# Bidirectional_Amp.net
KiCad netlist of a schematic drawn in EAGLE
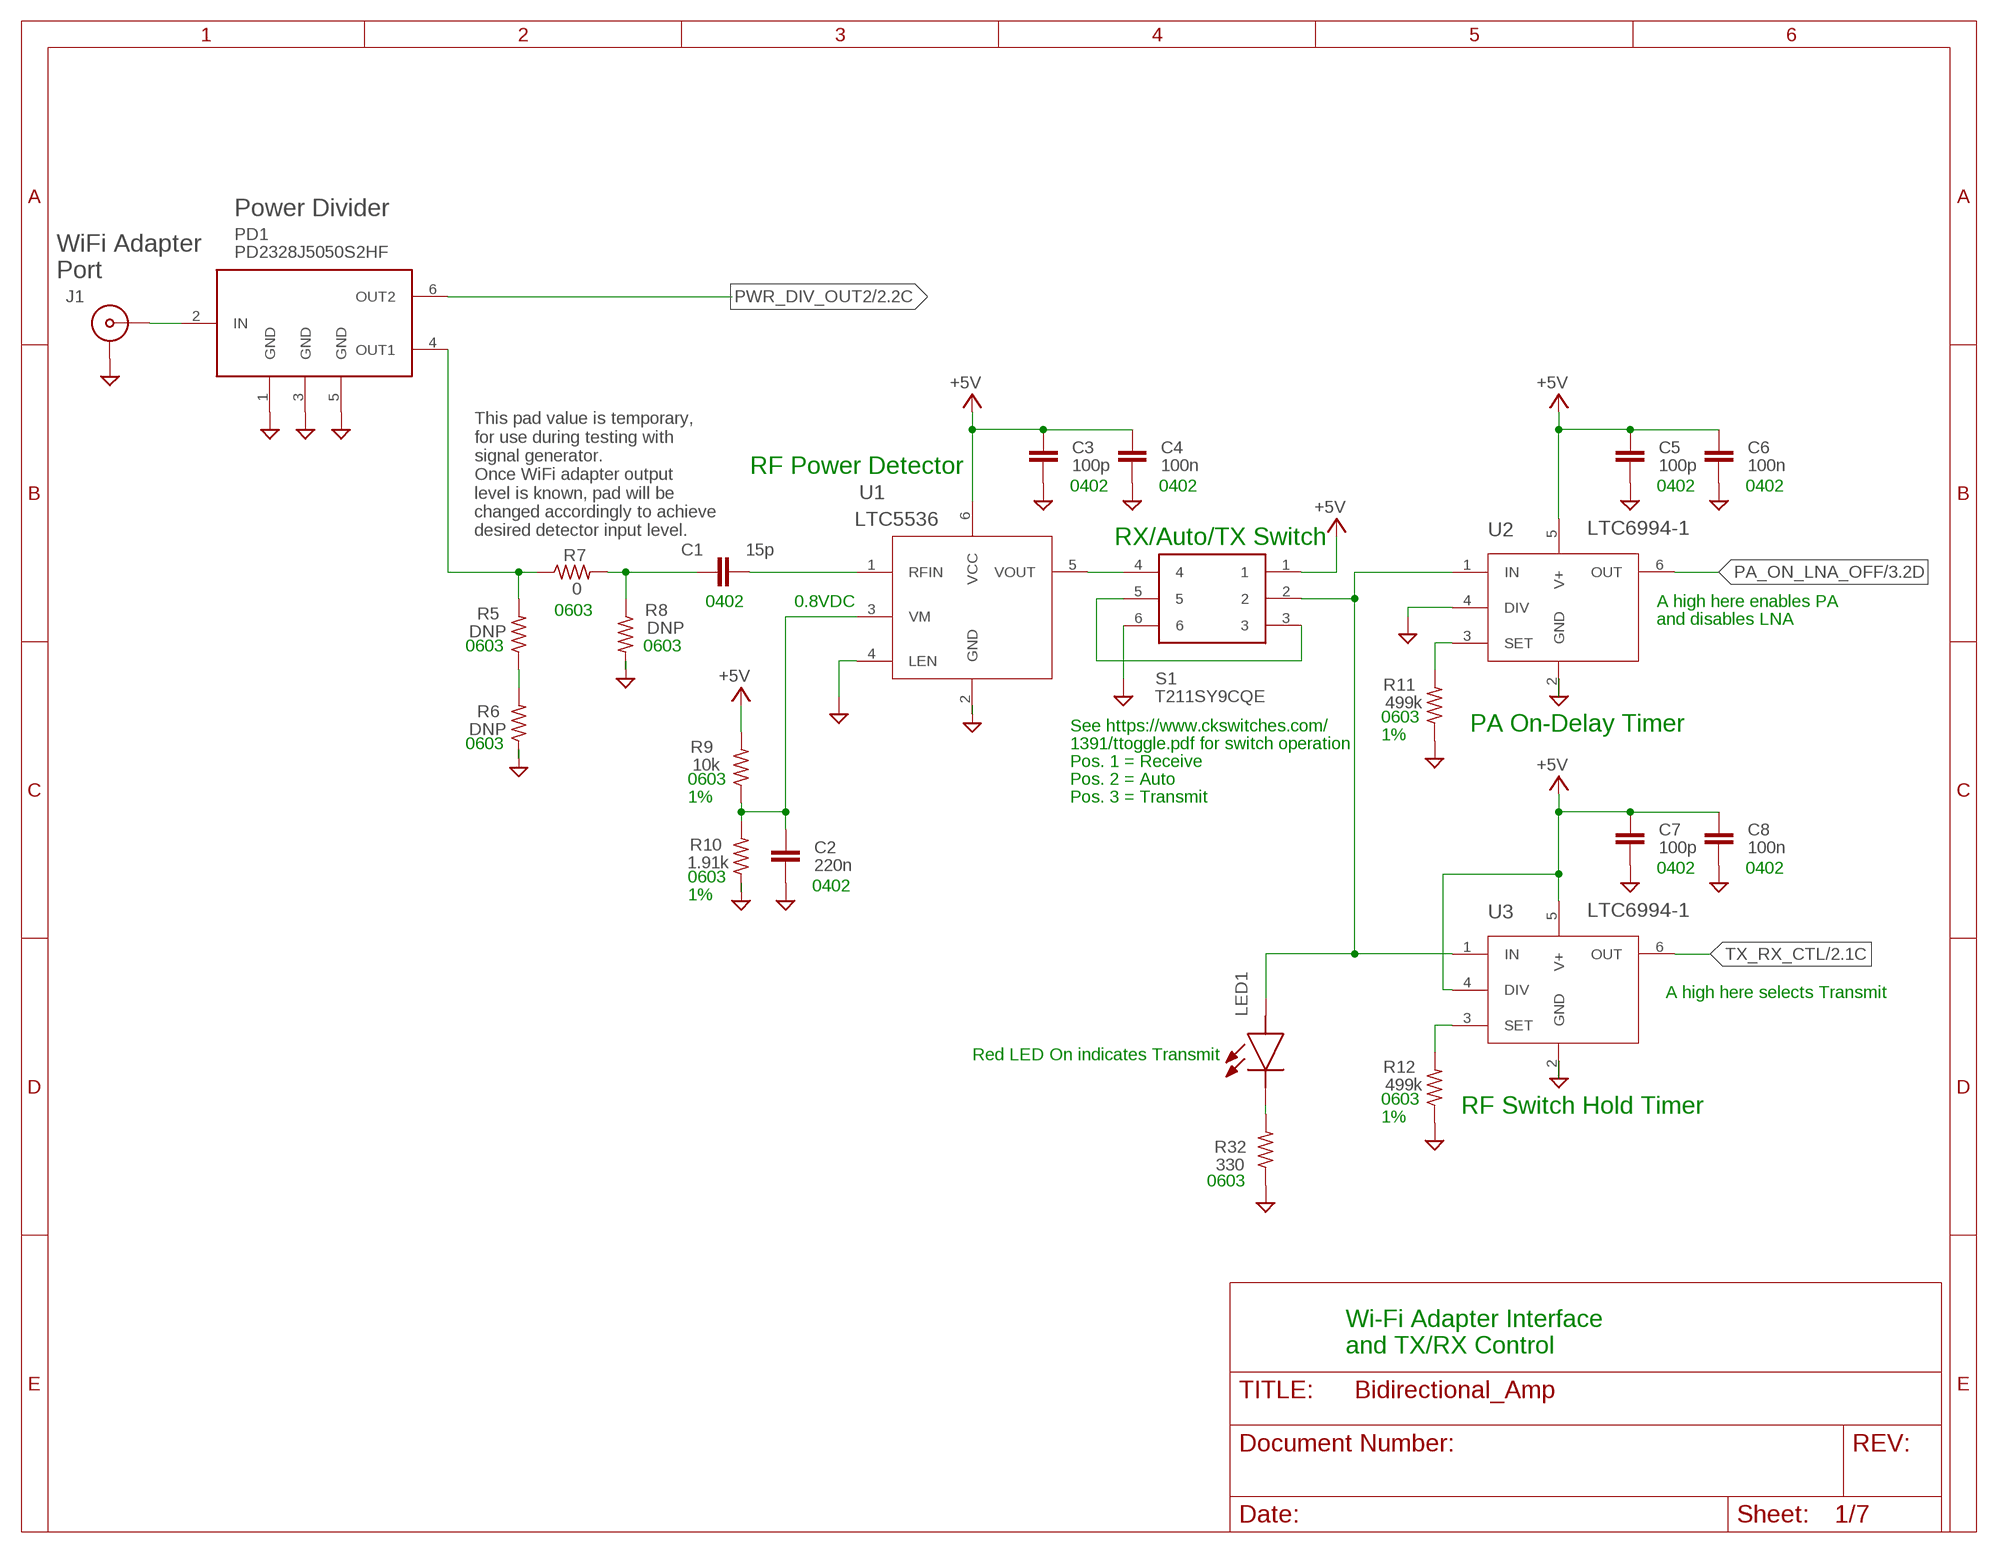
[diagram p0: schematic, sheet 1]
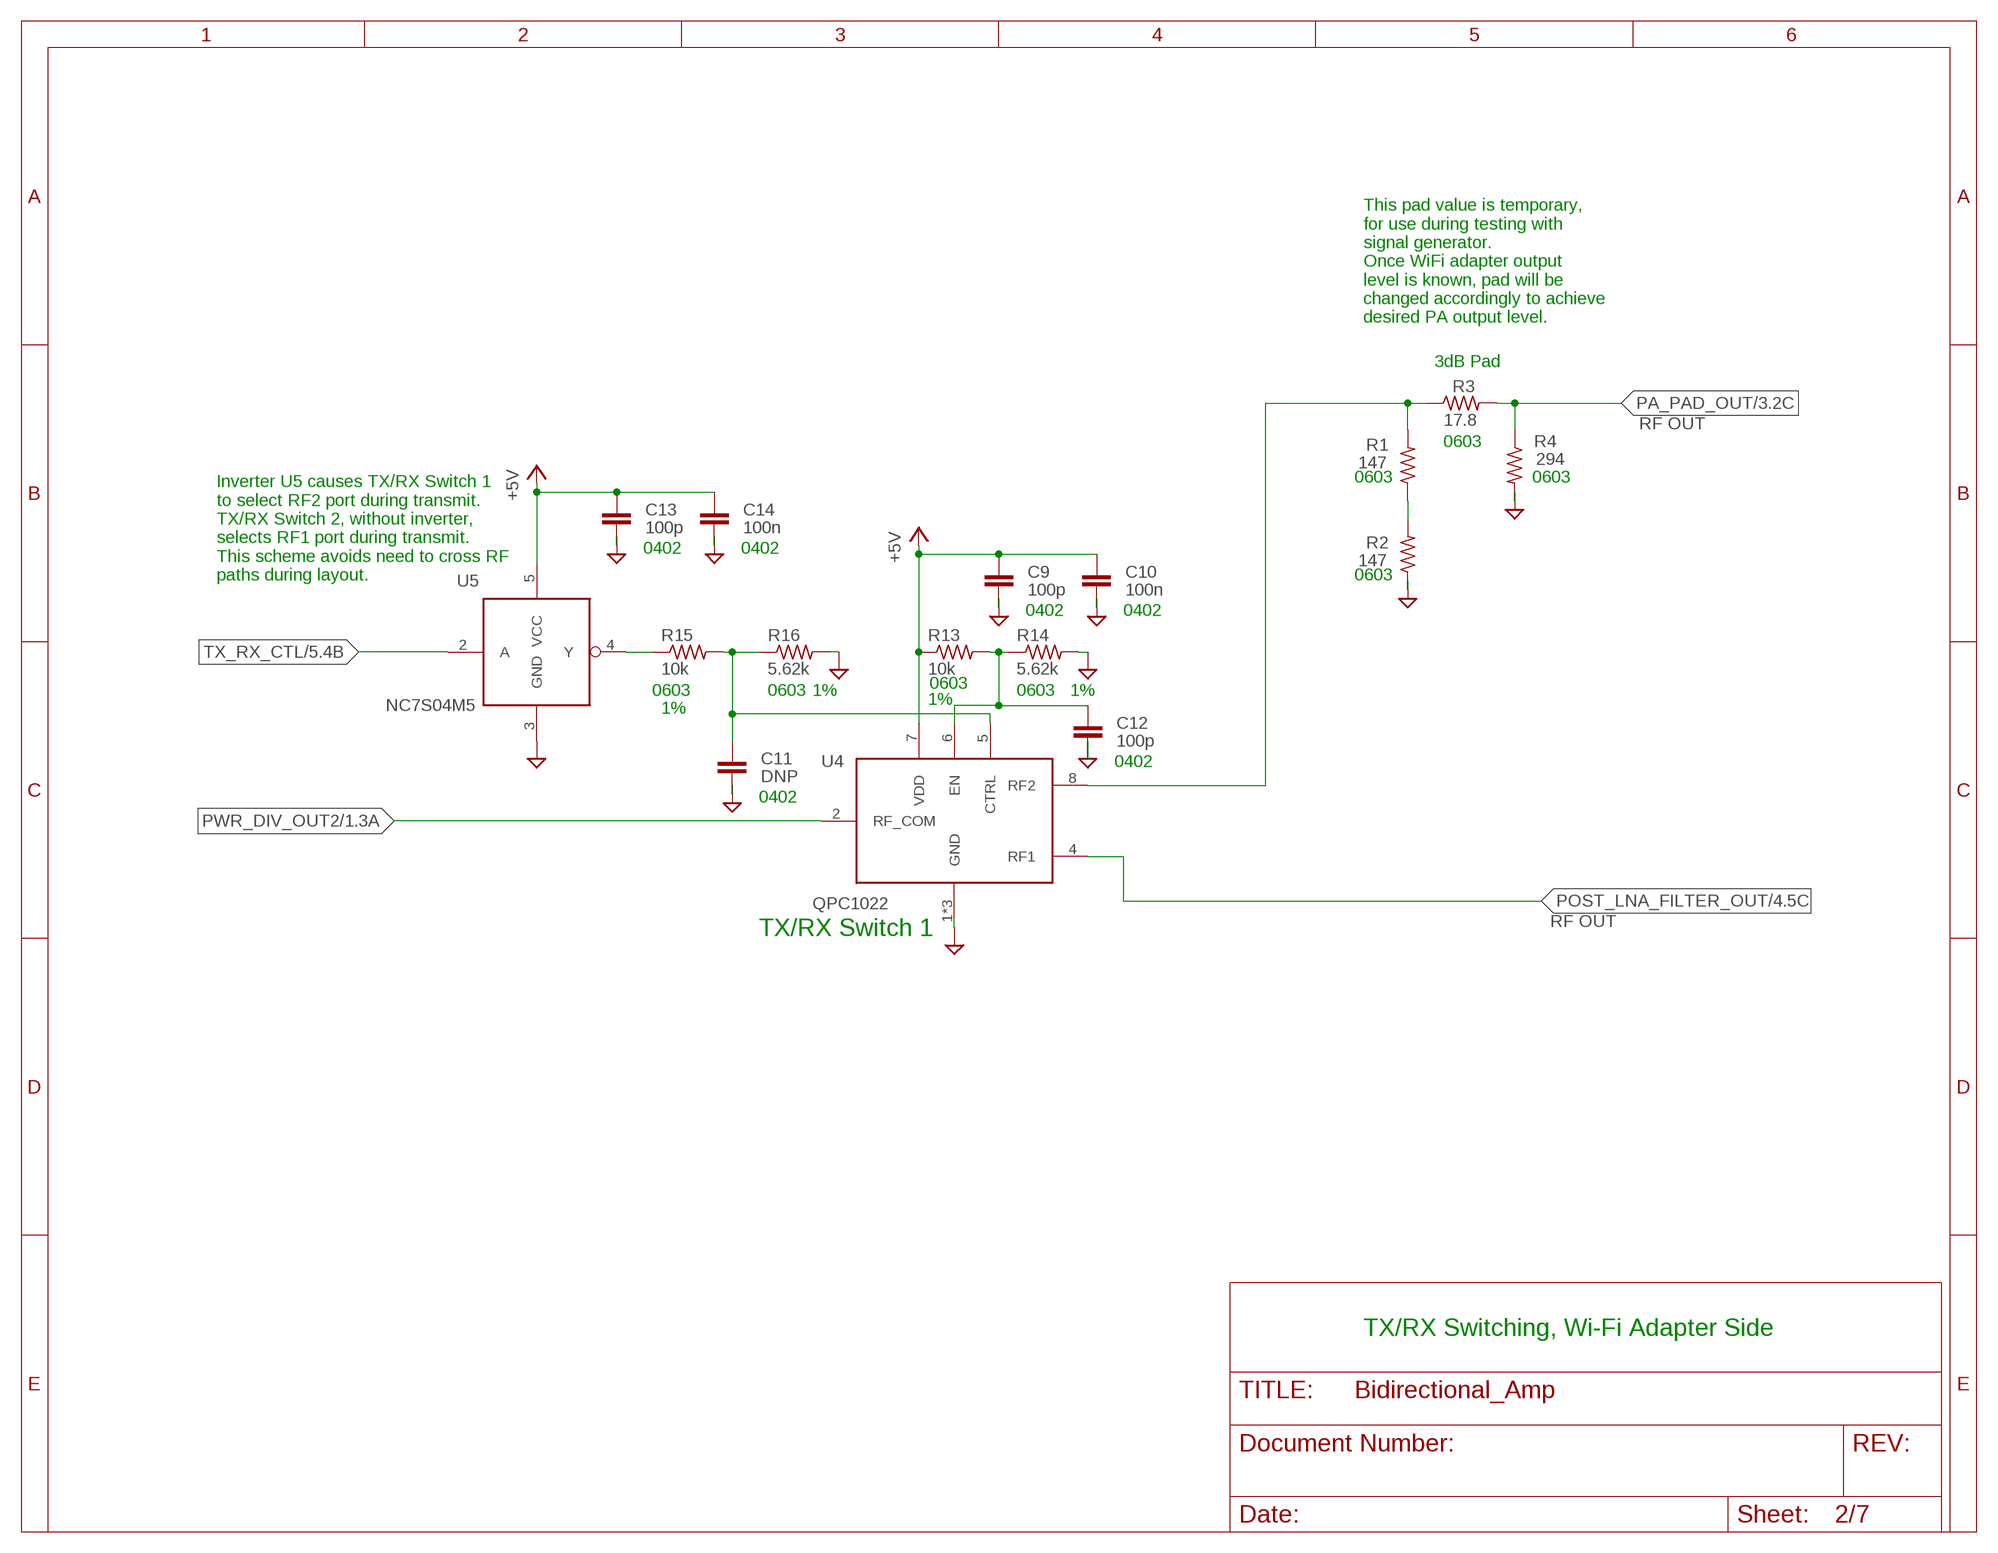
[diagram p1: schematic, sheet 2]
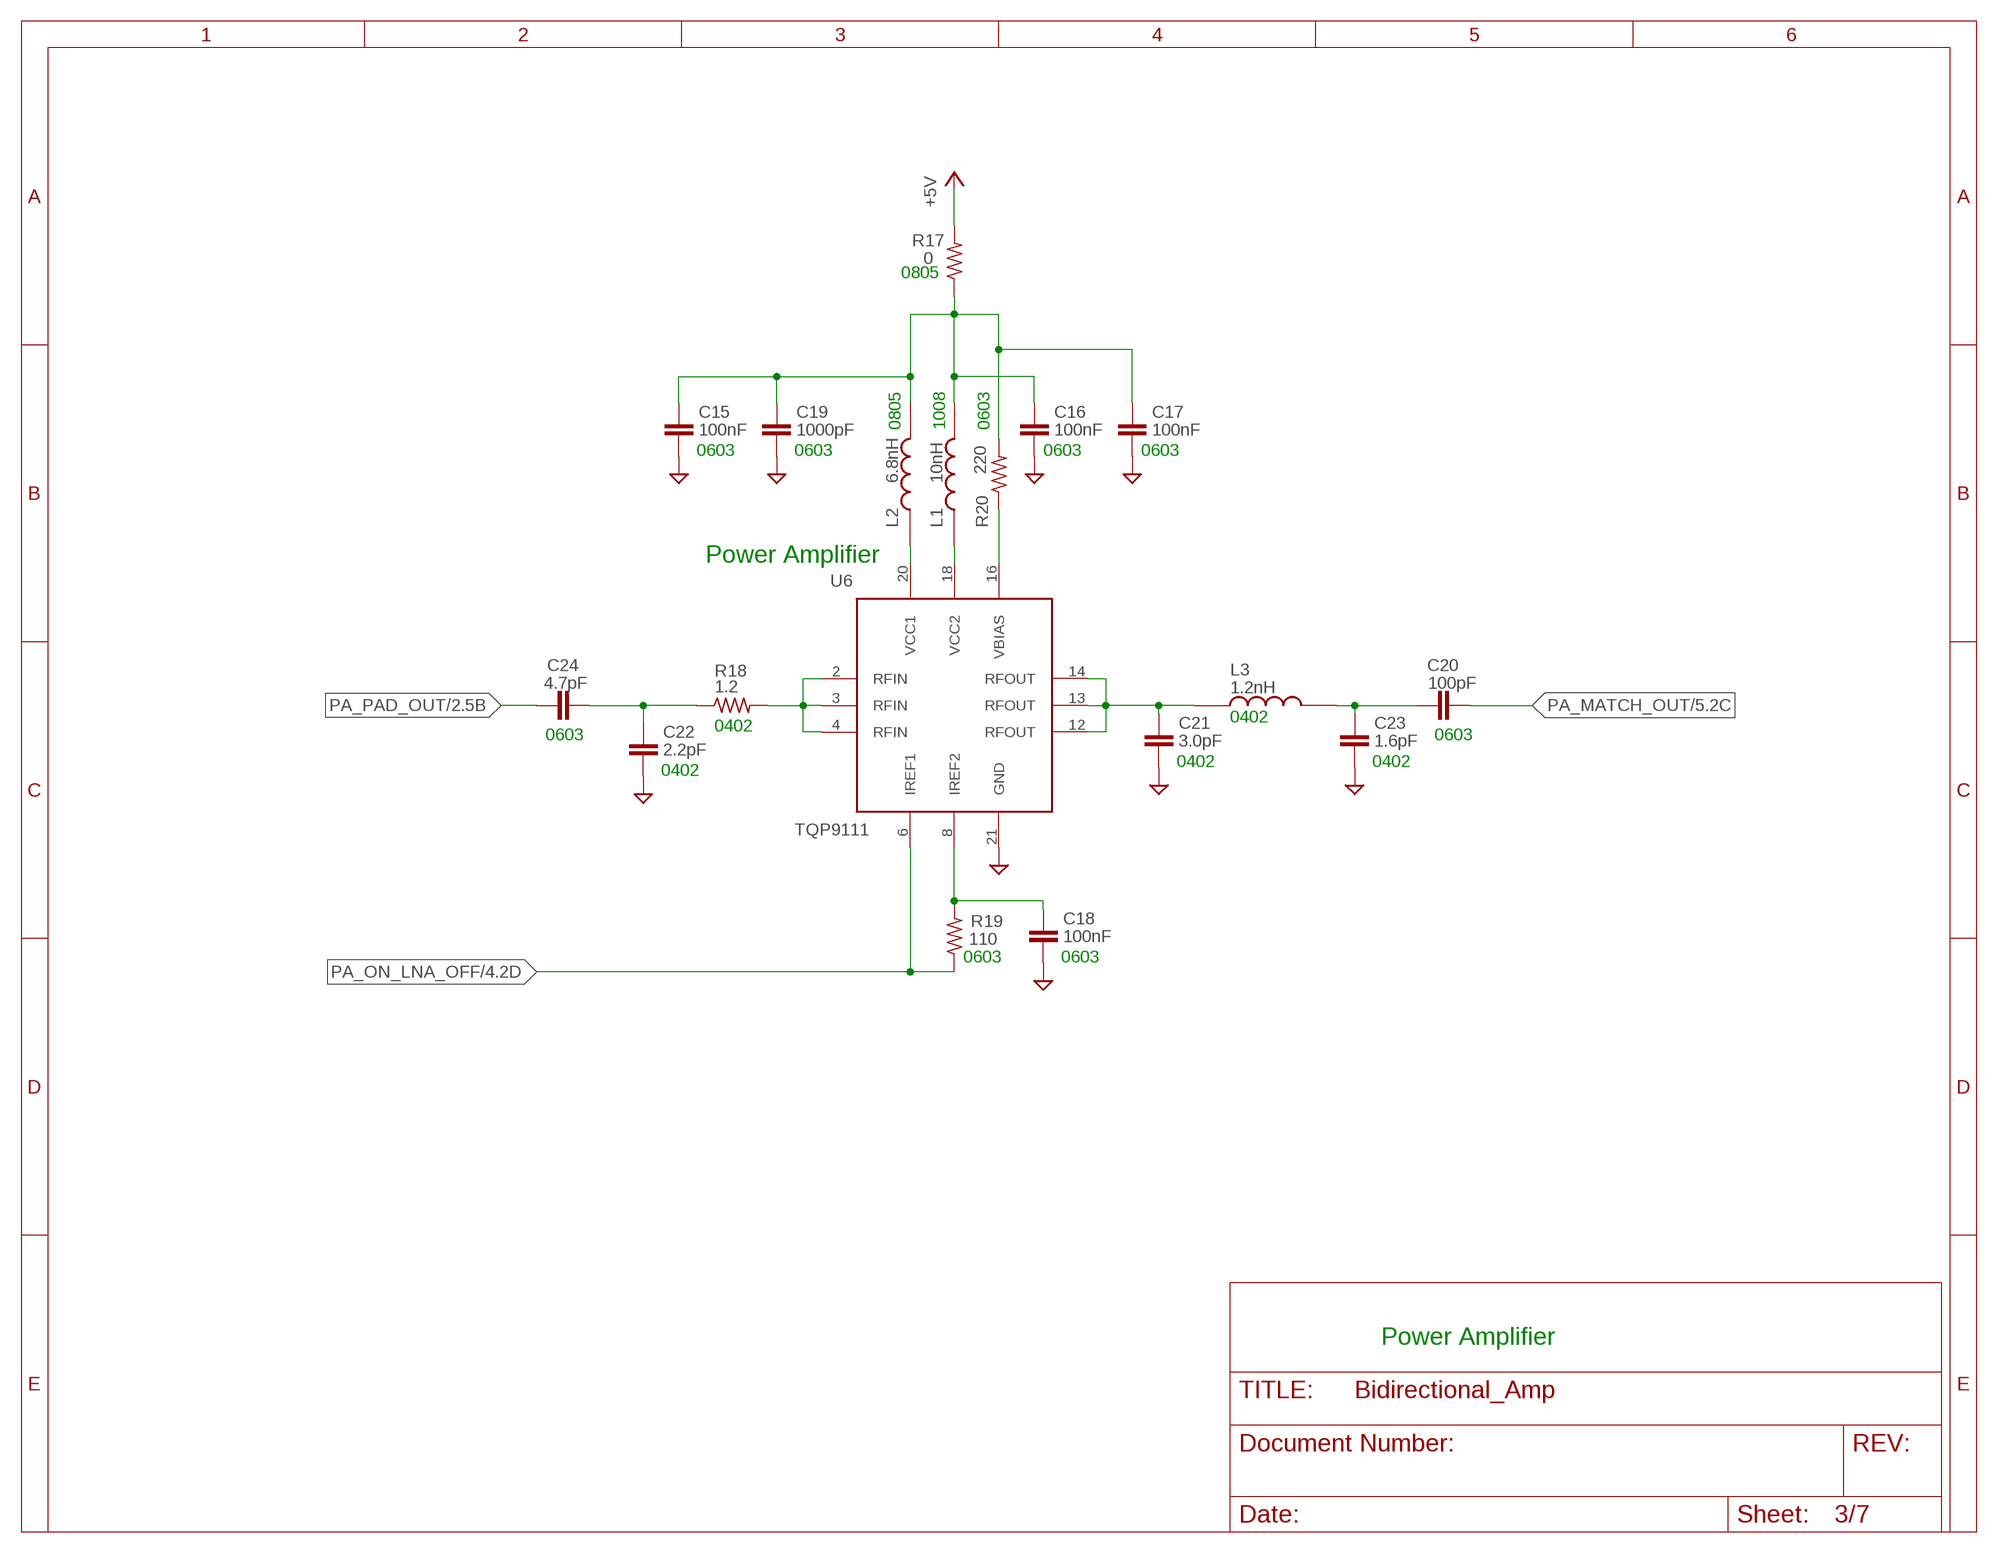
[diagram p2: schematic, sheet 3]
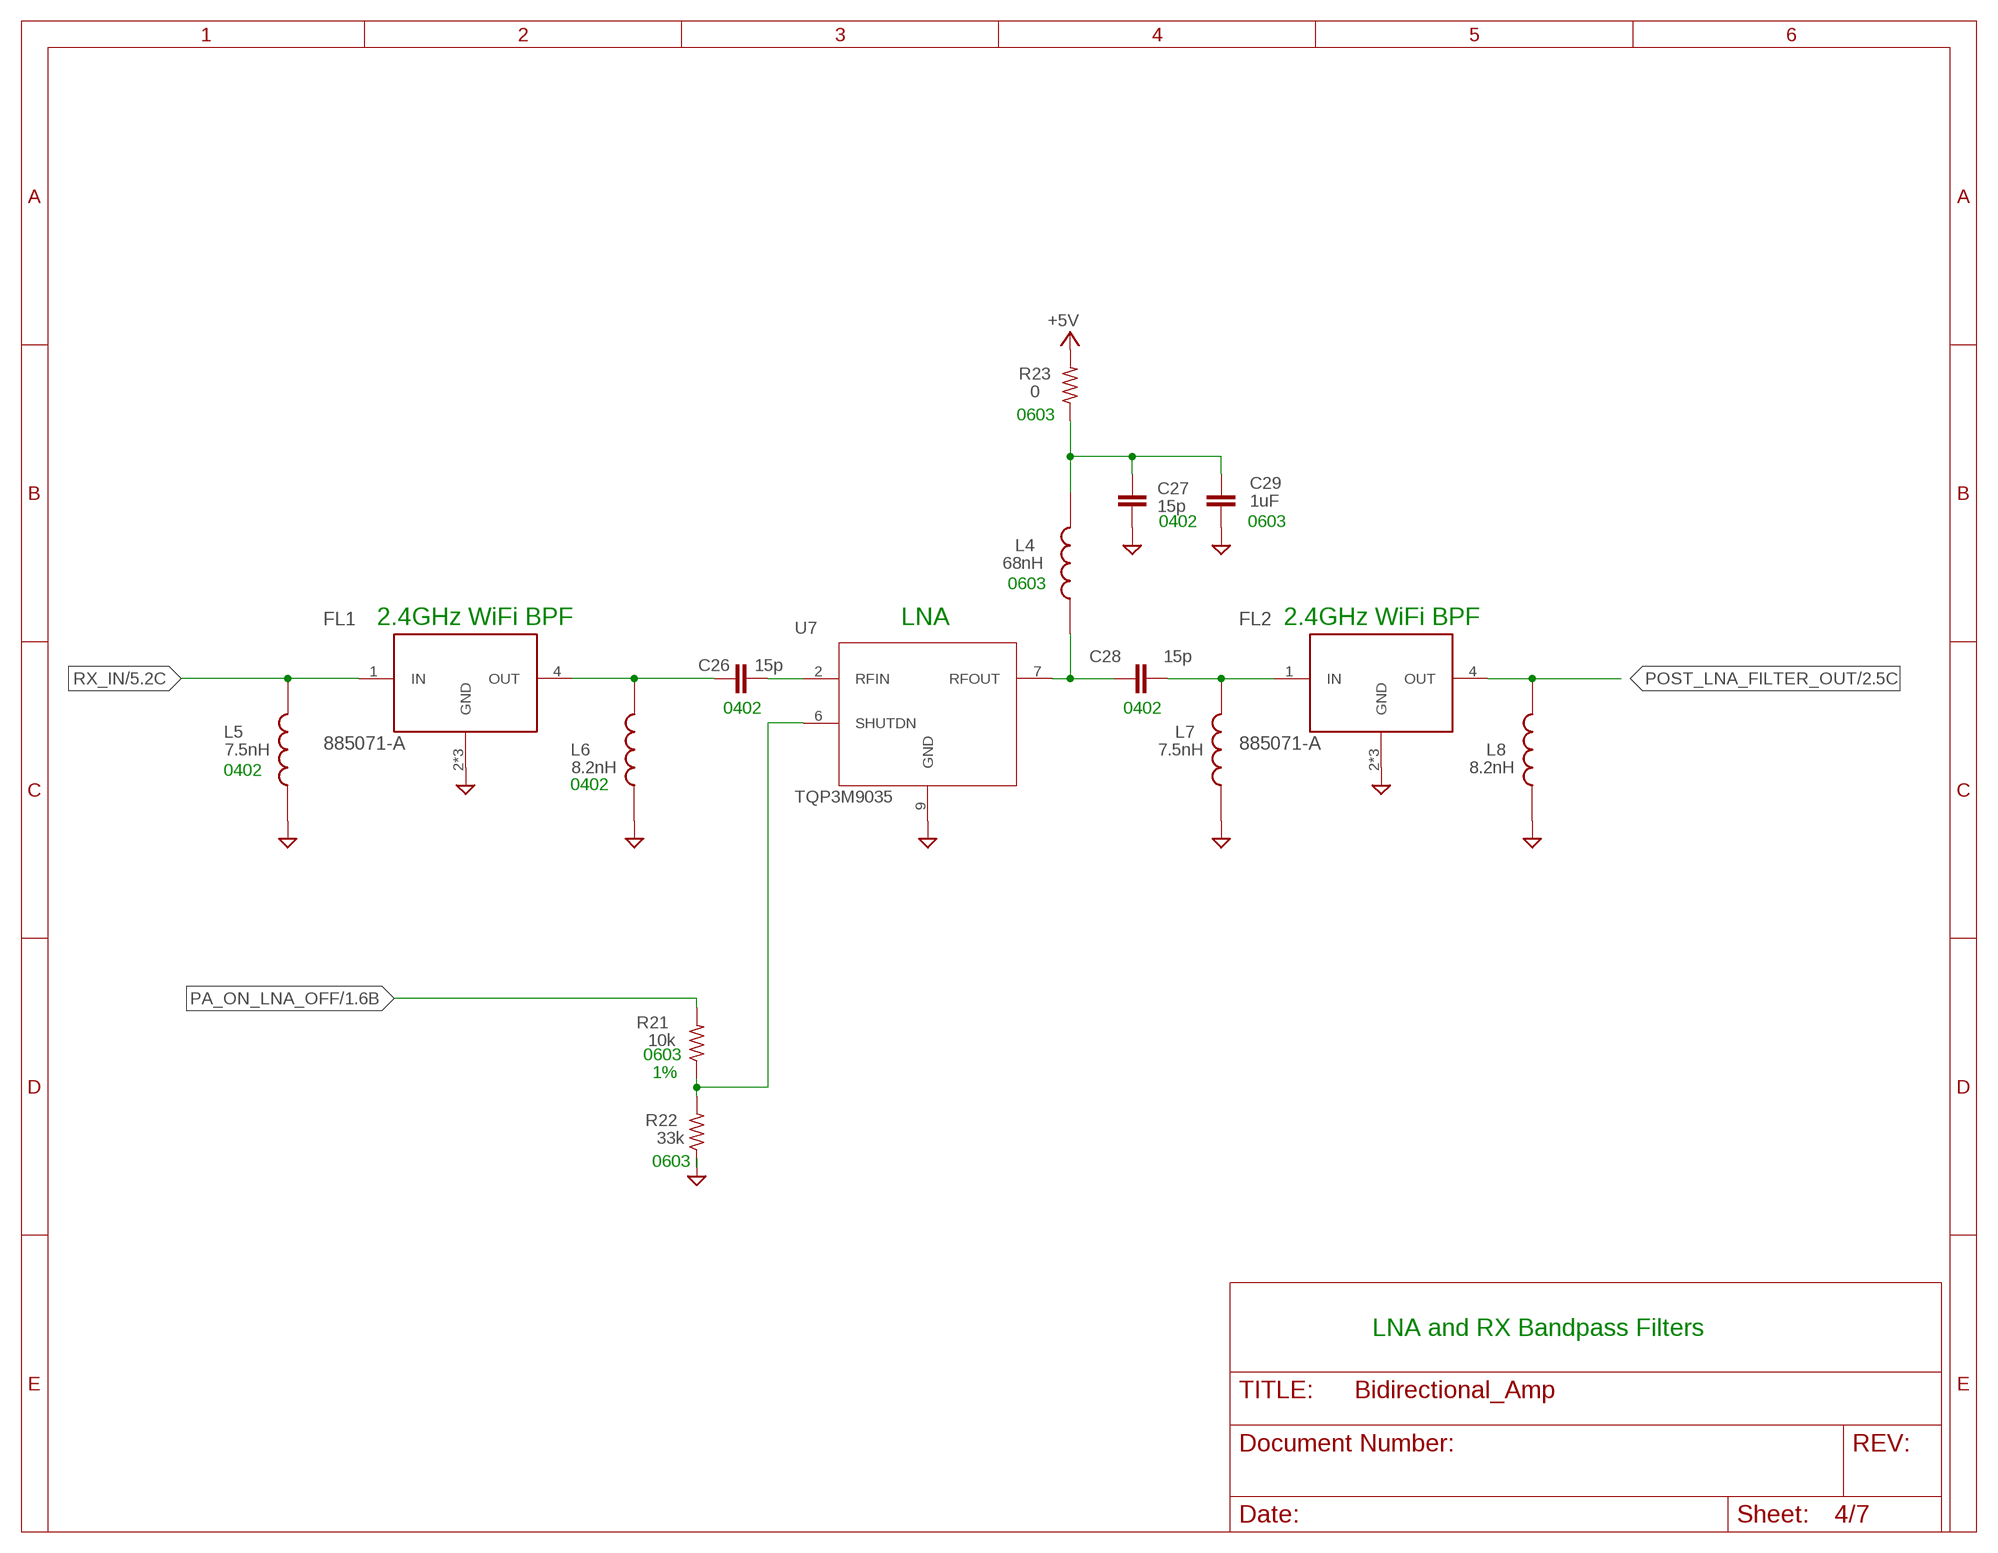
[diagram p3: schematic, sheet 4]
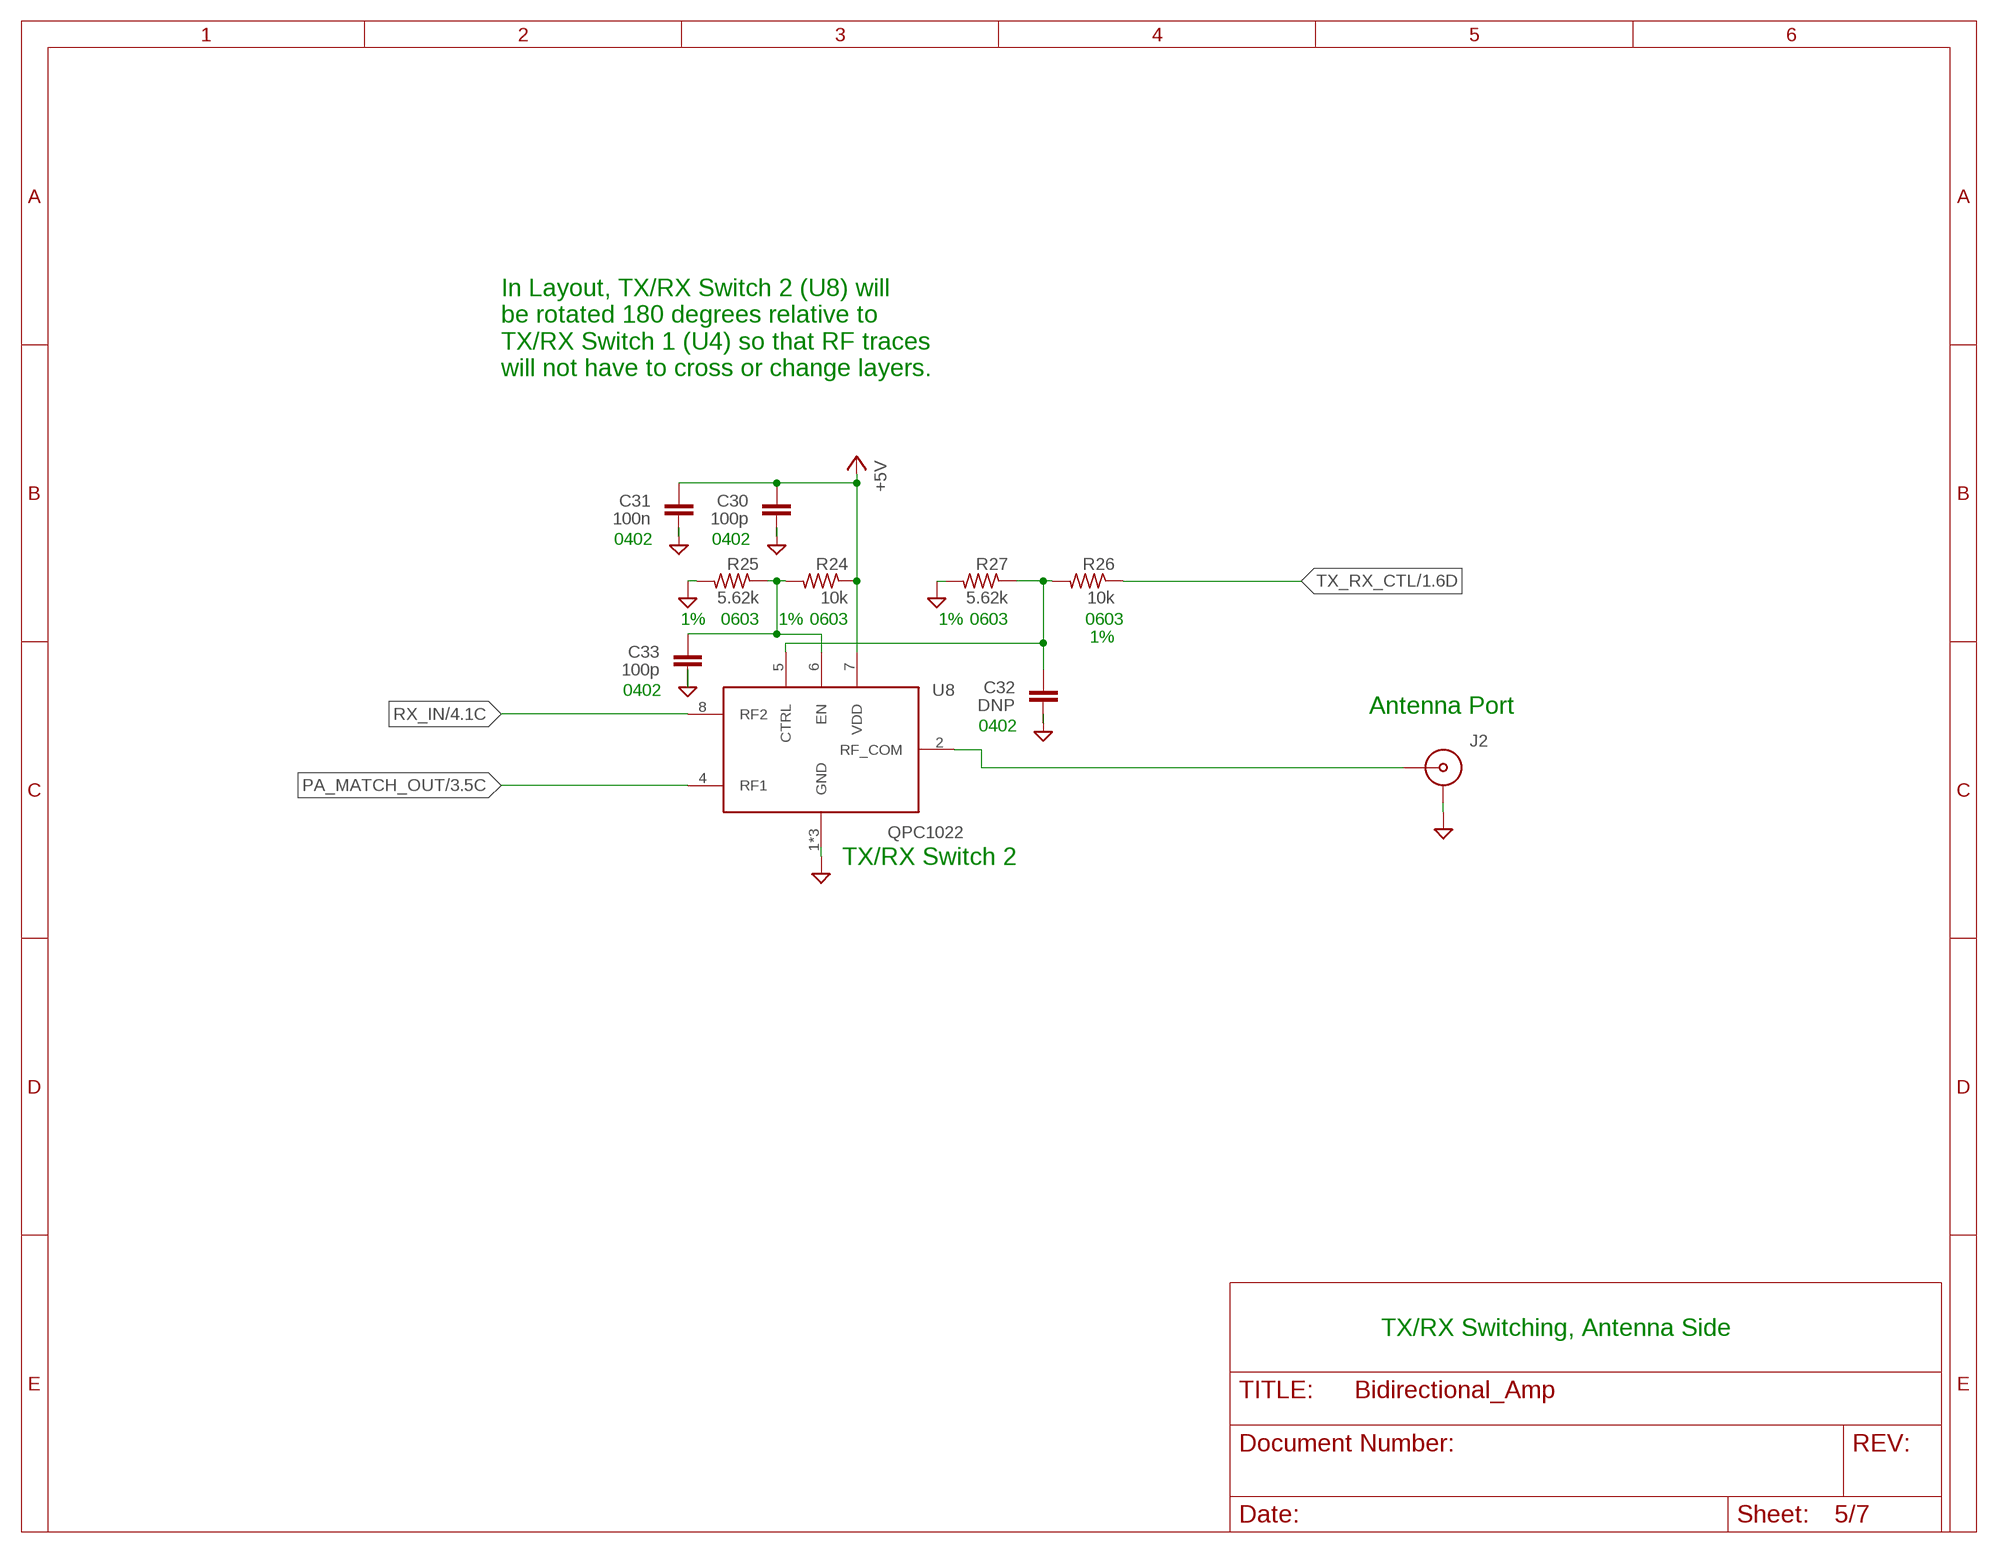
[diagram p4: schematic, sheet 5]
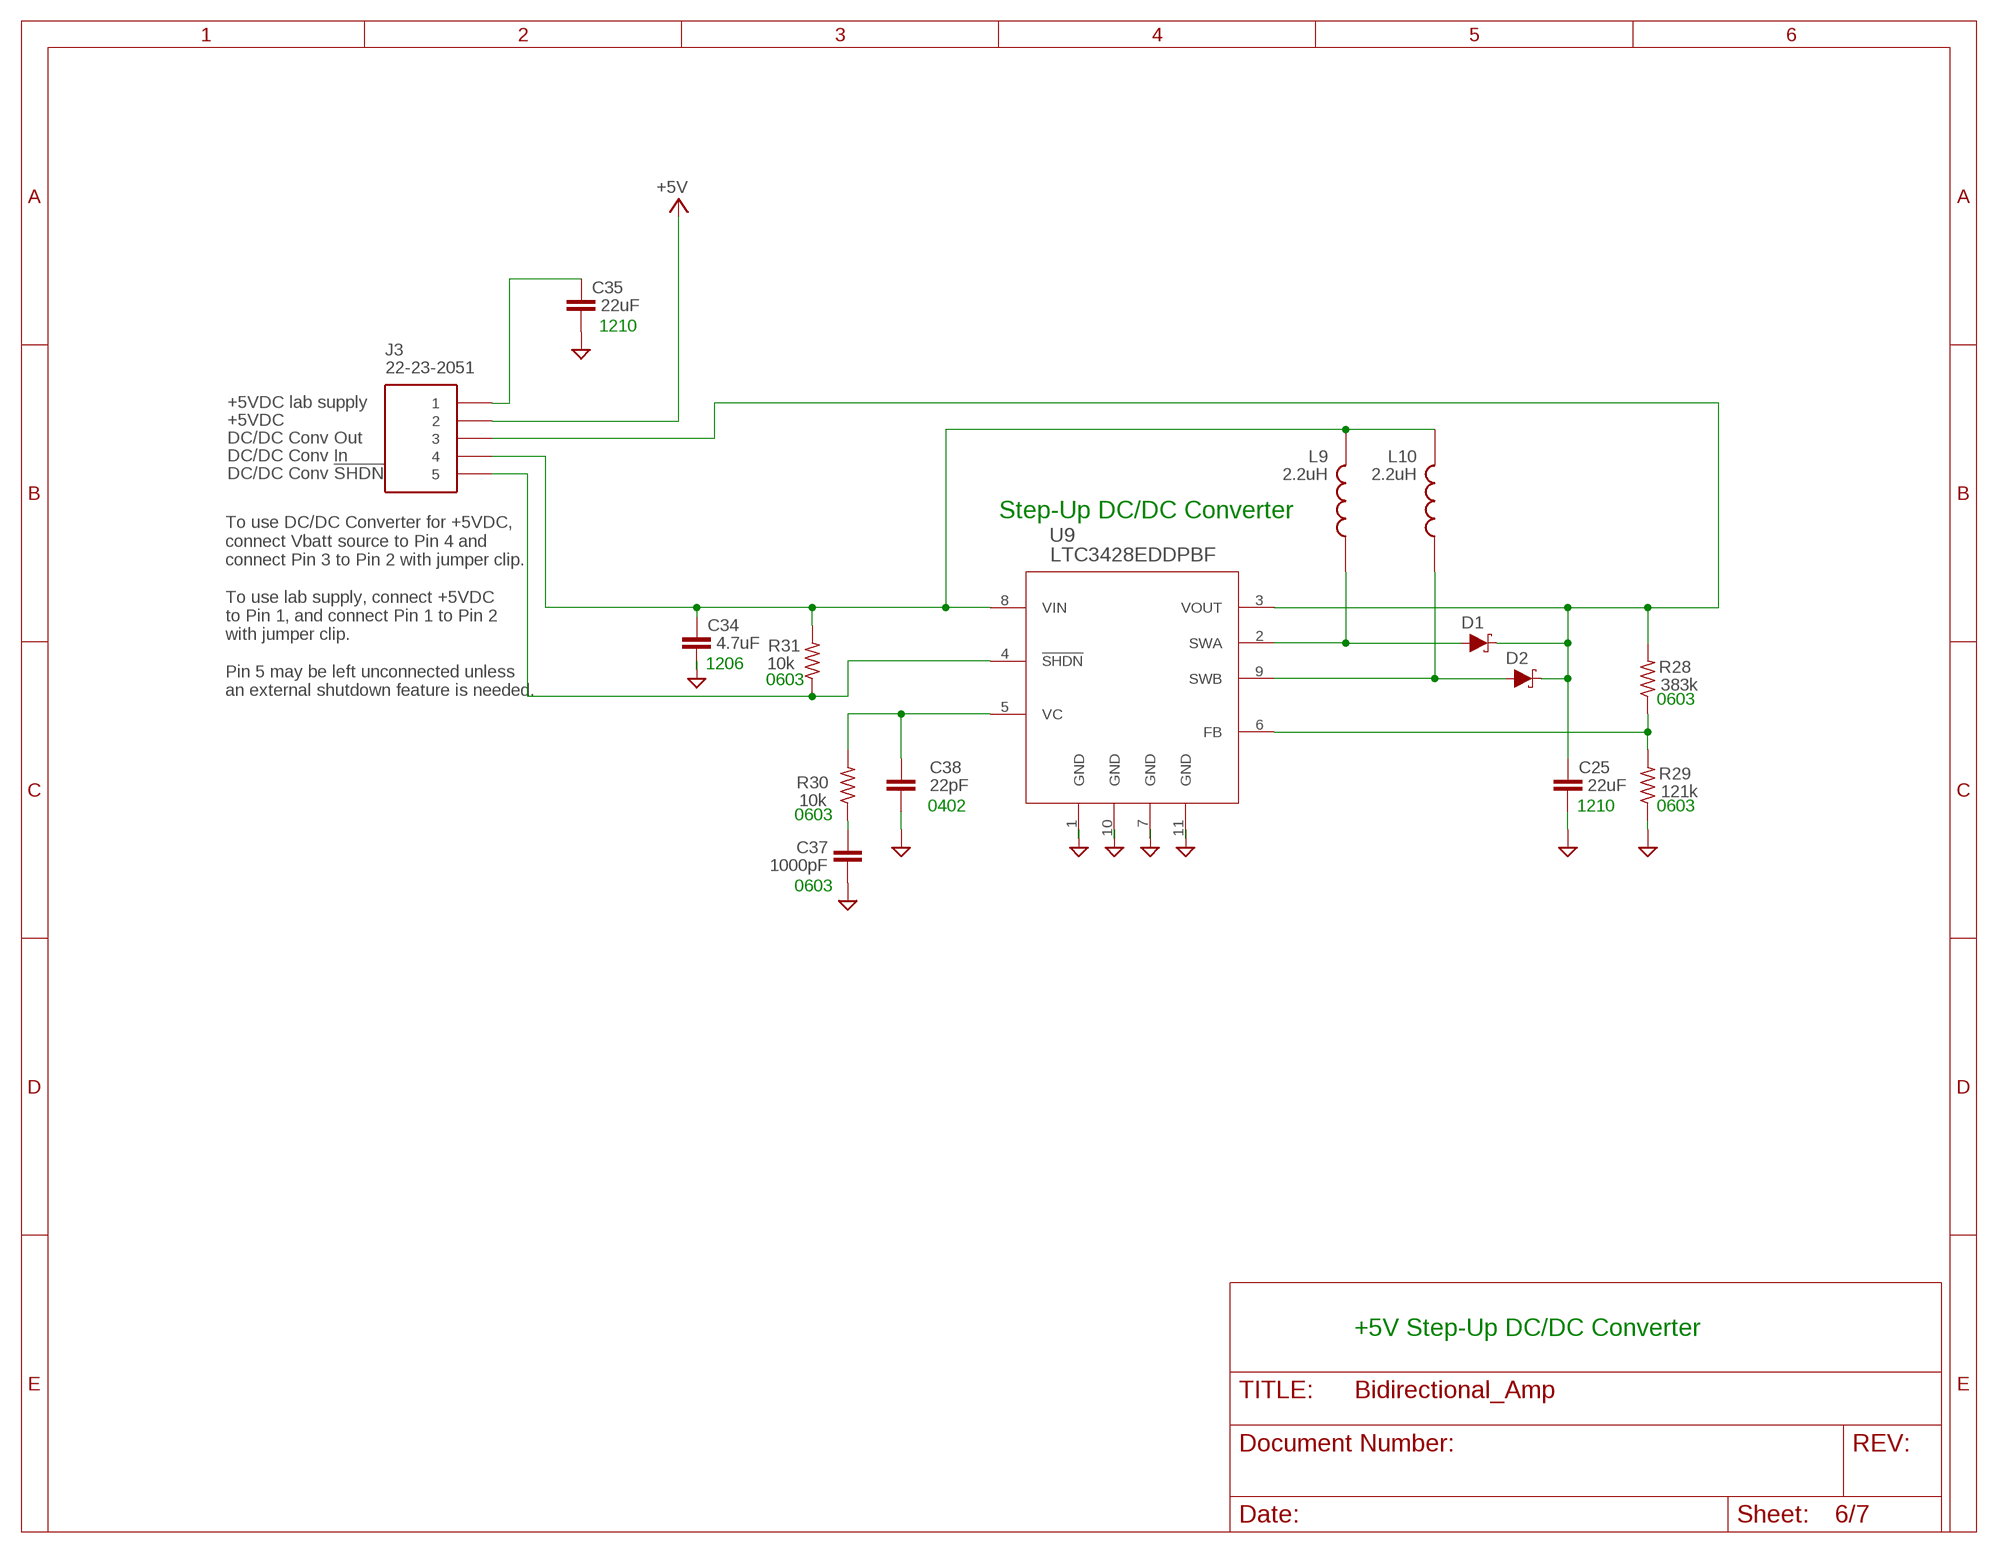
[diagram p5: schematic, sheet 6]
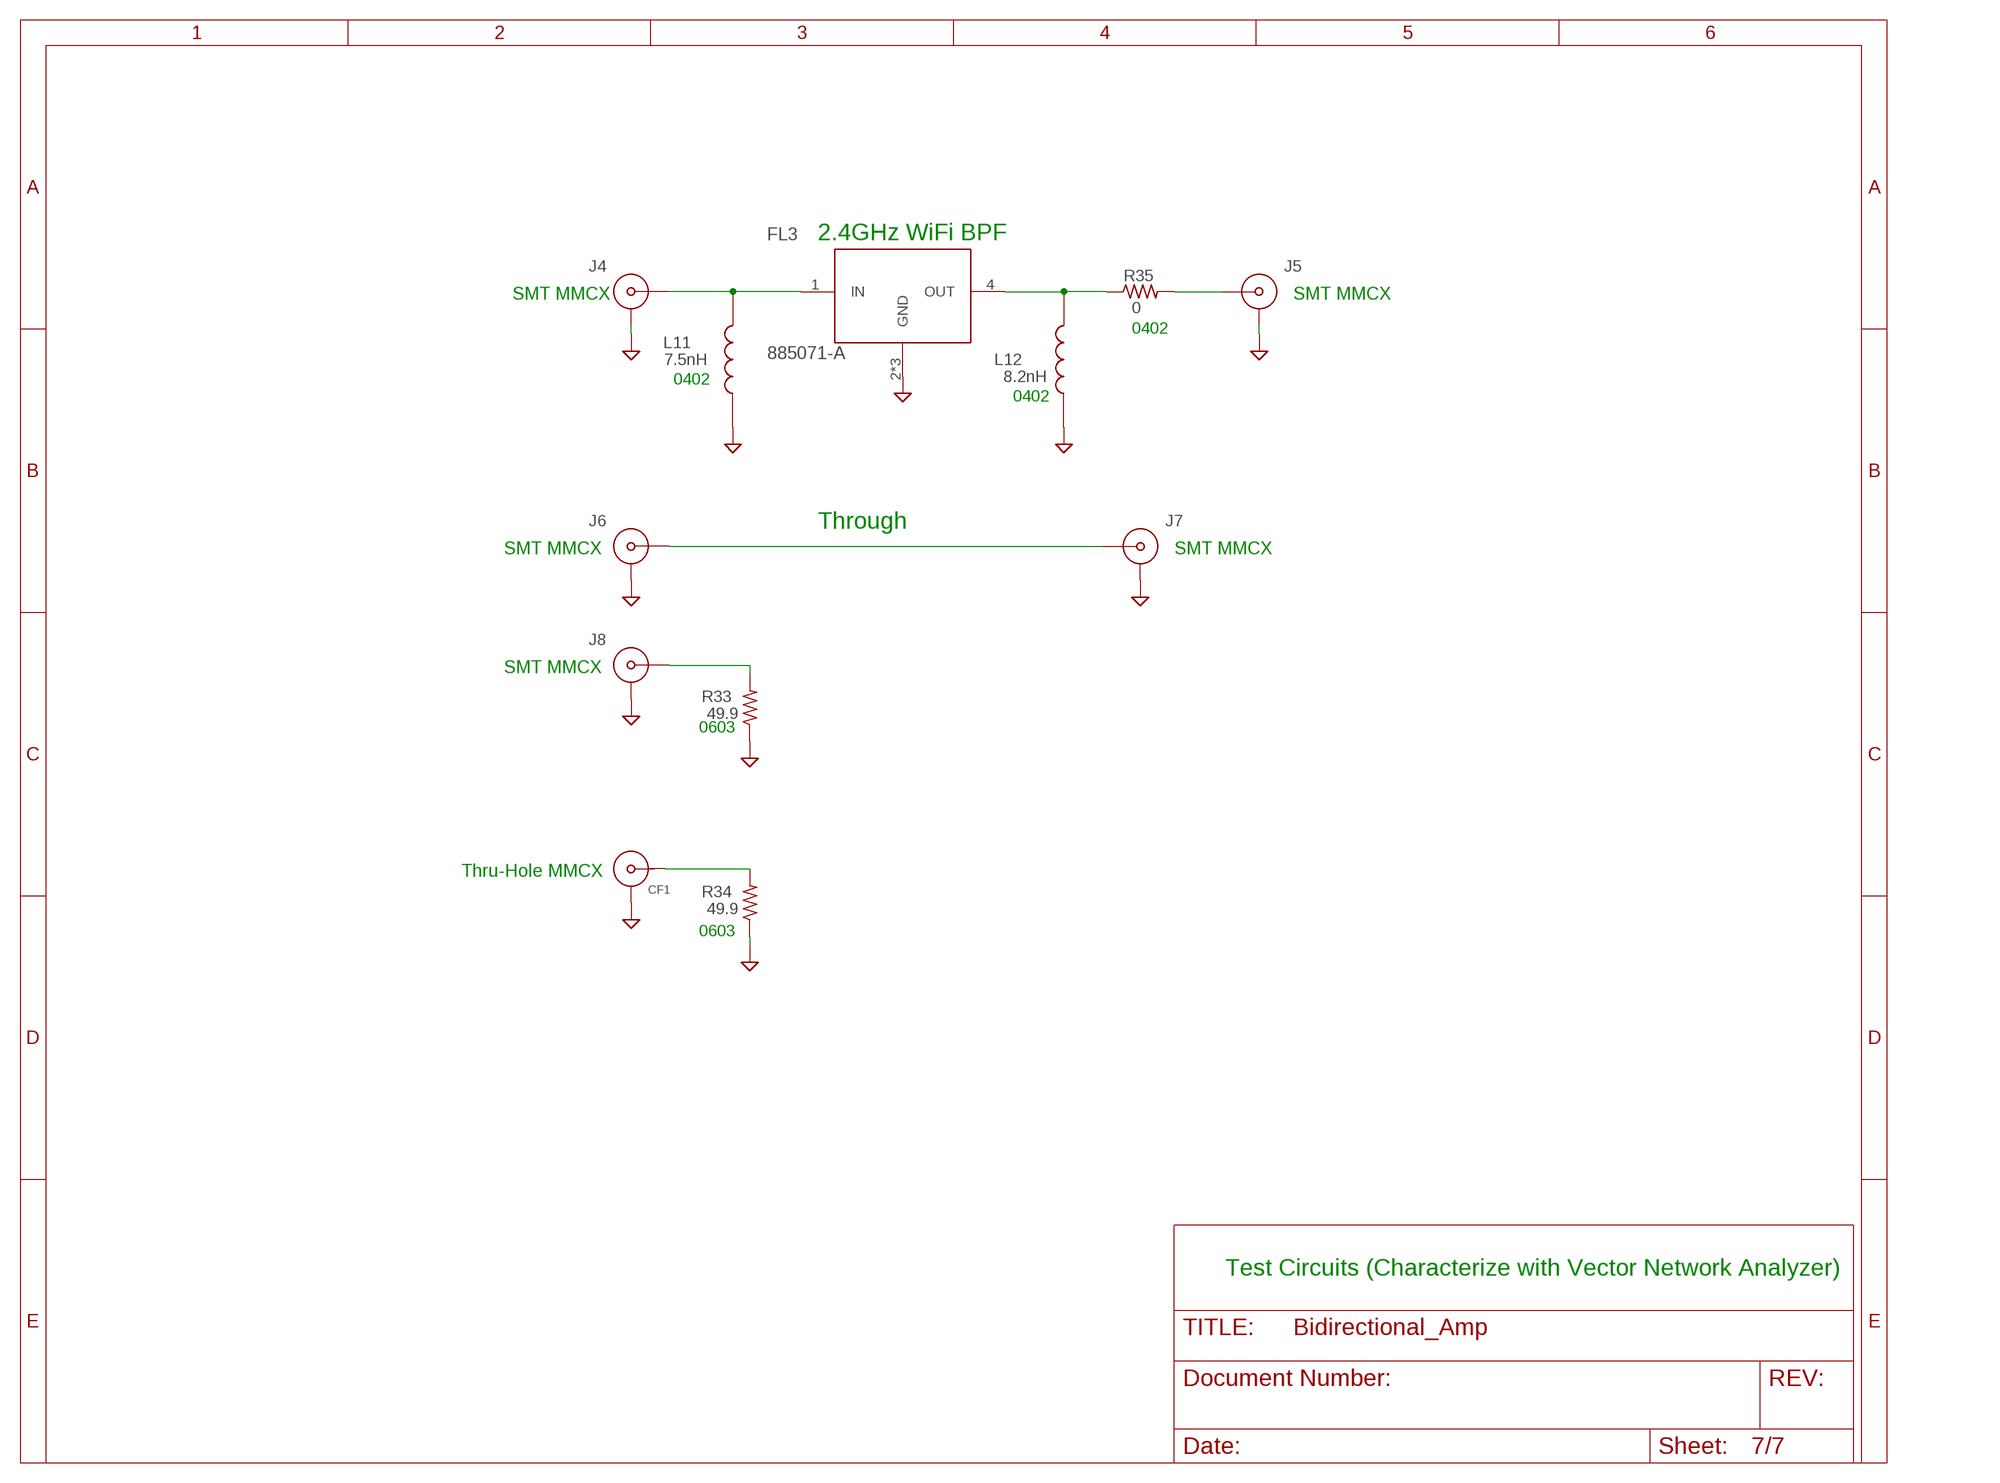
[diagram p6: schematic, sheet 7]

(export (version "E")
  (design (tool "Eeschema 10.0.6"))
  (components
    (comp (ref "C25")
      (value "22uF")
      (footprint "eagle-import:C1210")
      (fields (field (name "MPN") "GCJ32ER71C226KE01L"))
      (libsource (lib "eagle-import") (part "C-EUC1210"))
    )
    (comp (ref "C34")
      (value "4.7uF")
      (footprint "eagle-import:C1206")
      (fields (field (name "MPN") "GCJ31CR71C475KA01L") (field (name "VOLTAGE") "16V"))
      (libsource (lib "eagle-import") (part "C-EUC1206"))
    )
    (comp (ref "C35")
      (value "22uF")
      (footprint "eagle-import:C1210")
      (fields (field (name "MPN") "GCJ32ER71C226KE01L"))
      (libsource (lib "eagle-import") (part "C-EUC1210"))
    )
    (comp (ref "C37")
      (value "1000pF")
      (footprint "eagle-import:C0603")
      (fields (field (name "MPN") "CGA3E2C0G1H102J080AA"))
      (libsource (lib "eagle-import") (part "C-EUC0603"))
    )
    (comp (ref "C38")
      (value "22pF")
      (footprint "eagle-import:C0402")
      (fields (field (name "MPN") "GCM1555C1H220JA16J"))
      (libsource (lib "eagle-import") (part "C-EUC0402"))
    )
    (comp (ref "D1")
      (value "DIODE-SCHOTTKY-PMEG4005EJ")
      (footprint "eagle-import:SOD-323")
      (fields (field (name "MPN") "PMEG1020EJ,115"))
      (libsource (lib "eagle-import") (part "DIODE-SCHOTTKY-PMEG4005EJ"))
    )
    (comp (ref "D2")
      (value "DIODE-SCHOTTKY-PMEG4005EJ")
      (footprint "eagle-import:SOD-323")
      (fields (field (name "MPN") "PMEG1020EJ,115"))
      (libsource (lib "eagle-import") (part "DIODE-SCHOTTKY-PMEG4005EJ"))
    )
    (comp (ref "J3")
      (value "22-23-2051")
      (footprint "eagle-import:HDRV5W107P0X254_1X5_1255X635X8")
      (libsource (lib "eagle-import") (part "22-23-2051"))
    )
    (comp (ref "L9")
      (value "2.2uH")
      (footprint "eagle-import:XFL4020-222ME")
      (fields (field (name "MANUFACTURER_PART_NUMBER") "XFL4020-222MEB"))
      (libsource (lib "eagle-import") (part "XFL4020-222MEB"))
    )
    (comp (ref "L10")
      (value "2.2uH")
      (footprint "eagle-import:XFL4020-222ME")
      (fields (field (name "MANUFACTURER_PART_NUMBER") "XFL4020-222MEB"))
      (libsource (lib "eagle-import") (part "XFL4020-222MEB"))
    )
    (comp (ref "R28")
      (value "383k")
      (footprint "eagle-import:.0603-B-NOSILK")
      (fields (field (name "MPN") "ERJ-3EKF3833V"))
      (libsource (lib "eagle-import") (part "rcl_custom_R-US_0603-B-NOSILK"))
    )
    (comp (ref "R29")
      (value "121k")
      (footprint "eagle-import:.0603-B-NOSILK")
      (fields (field (name "MPN") "ERJ-3EKF1213V "))
      (libsource (lib "eagle-import") (part "rcl_custom_R-US_0603-B-NOSILK"))
    )
    (comp (ref "R30")
      (value "10k")
      (footprint "eagle-import:.0603-B-NOSILK")
      (fields (field (name "MPN") "ERJ-3EKF1002V"))
      (libsource (lib "eagle-import") (part "rcl_custom_R-US_0603-B-NOSILK"))
    )
    (comp (ref "R31")
      (value "10k")
      (footprint "eagle-import:.0603-B-NOSILK")
      (fields (field (name "MPN") "ERJ-3GEYJ103V"))
      (libsource (lib "eagle-import") (part "rcl_custom_R-US_0603-B-NOSILK"))
    )
    (comp (ref "U9")
      (value "LTC3428EDDPBF")
      (footprint "eagle-import:DFN-10_DD")
      (fields (field (name "MANUFACTURER_PART_NUMBER") "LTC3428EDD#PBF"))
      (libsource (lib "eagle-import") (part "LTC3428EDDPBF"))
    )
    (comp (ref "C1")
      (value "15p")
      (footprint "eagle-import:C0402")
      (fields (field (name "MPN") "GJM1555C1H150JB01D "))
      (libsource (lib "eagle-import") (part "C-EUC0402"))
    )
    (comp (ref "C2")
      (value "220n")
      (footprint "eagle-import:C0402")
      (fields (field (name "MPN") "C1005X7R1C224K050BE "))
      (libsource (lib "eagle-import") (part "C-EUC0402"))
    )
    (comp (ref "C3")
      (value "100p")
      (footprint "eagle-import:C0402")
      (fields (field (name "MPN") "GCM1555C1H101JA16D "))
      (libsource (lib "eagle-import") (part "C-EUC0402"))
    )
    (comp (ref "C4")
      (value "100n")
      (footprint "eagle-import:C0402")
      (fields (field (name "MPN") "CGA2B1X7R1C104K050BC"))
      (libsource (lib "eagle-import") (part "C-EUC0402"))
    )
    (comp (ref "C5")
      (value "100p")
      (footprint "eagle-import:C0402")
      (fields (field (name "MPN") "GCM1555C1H101JA16D "))
      (libsource (lib "eagle-import") (part "C-EUC0402"))
    )
    (comp (ref "C6")
      (value "100n")
      (footprint "eagle-import:C0402")
      (fields (field (name "MPN") "CGA2B1X7R1C104K050BC"))
      (libsource (lib "eagle-import") (part "C-EUC0402"))
    )
    (comp (ref "C7")
      (value "100p")
      (footprint "eagle-import:C0402")
      (fields (field (name "MPN") "GCM1555C1H101JA16D "))
      (libsource (lib "eagle-import") (part "C-EUC0402"))
    )
    (comp (ref "C8")
      (value "100n")
      (footprint "eagle-import:C0402")
      (fields (field (name "MPN") "CGA2B1X7R1C104K050BC"))
      (libsource (lib "eagle-import") (part "C-EUC0402"))
    )
    (comp (ref "J1")
      (value "73415-2061")
      (footprint "eagle-import:73415-2063")
      (fields (field (name "MPN") "0734152061") (field (name "MPN_1") "0734152061"))
      (libsource (lib "eagle-import") (part "73415-2061"))
    )
    (comp (ref "LED1")
      (value "VLMK3102-GS08")
      (footprint "eagle-import:PLCC-2")
      (libsource (lib "eagle-import") (part "VLMK3102-GS08"))
    )
    (comp (ref "PD1")
      (value "PD2328J5050S2HF")
      (footprint "eagle-import:PSON65P204X129X58-6N")
      (libsource (lib "eagle-import") (part "PD2328J5050S2HF"))
    )
    (comp (ref "R5")
      (value "DNP")
      (footprint "eagle-import:R0603")
      (libsource (lib "eagle-import") (part "rcl_334_R-US_R0603"))
    )
    (comp (ref "R6")
      (value "DNP")
      (footprint "eagle-import:R0603")
      (libsource (lib "eagle-import") (part "rcl_334_R-US_R0603"))
    )
    (comp (ref "R7")
      (value "0")
      (footprint "eagle-import:R0603")
      (fields (field (name "MPN") "ERJ-3GEY0R00V"))
      (libsource (lib "eagle-import") (part "rcl_334_R-US_R0603"))
    )
    (comp (ref "R8")
      (value "DNP")
      (footprint "eagle-import:R0603")
      (libsource (lib "eagle-import") (part "rcl_334_R-US_R0603"))
    )
    (comp (ref "R9")
      (value "10k")
      (footprint "eagle-import:R0603")
      (fields (field (name "MPN") "ERJ-3EKF1002V "))
      (libsource (lib "eagle-import") (part "rcl_334_R-US_R0603"))
    )
    (comp (ref "R10")
      (value "1.91k")
      (footprint "eagle-import:R0603")
      (fields (field (name "MPN") "ERJ-3EKF1911V"))
      (libsource (lib "eagle-import") (part "rcl_334_R-US_R0603"))
    )
    (comp (ref "R11")
      (value "499k")
      (footprint "eagle-import:R0603")
      (fields (field (name "MPN") "CRCW0603499KFKEB"))
      (libsource (lib "eagle-import") (part "rcl_334_R-US_R0603"))
    )
    (comp (ref "R12")
      (value "499k")
      (footprint "eagle-import:R0603")
      (fields (field (name "MPN") "CRCW0603499KFKEB"))
      (libsource (lib "eagle-import") (part "rcl_334_R-US_R0603"))
    )
    (comp (ref "R32")
      (value "330")
      (footprint "eagle-import:R0603")
      (fields (field (name "MPN") "ESR03EZPJ331"))
      (libsource (lib "eagle-import") (part "rcl_334_R-US_R0603"))
    )
    (comp (ref "S1")
      (value "T211SY9CQE")
      (footprint "eagle-import:T201MH9V3BE")
      (libsource (lib "eagle-import") (part "T201MH9V3BE"))
    )
    (comp (ref "U1")
      (value "LTC5536")
      (footprint "eagle-import:TSOT-23_S6")
      (libsource (lib "eagle-import") (part "LTC5536ES6TRMPBF"))
    )
    (comp (ref "U2")
      (value "LTC6994-1")
      (footprint "eagle-import:TSOT-23_S6")
      (libsource (lib "eagle-import") (part "LTC6994CS6-1PBF"))
    )
    (comp (ref "U3")
      (value "LTC6994-1")
      (footprint "eagle-import:TSOT-23_S6")
      (libsource (lib "eagle-import") (part "LTC6994CS6-1PBF"))
    )
    (comp (ref "C30")
      (value "100p")
      (footprint "eagle-import:C0402")
      (fields (field (name "MPN") "GCM1555C1H101JA16D "))
      (libsource (lib "eagle-import") (part "C-EUC0402"))
    )
    (comp (ref "C31")
      (value "100n")
      (footprint "eagle-import:C0402")
      (fields (field (name "MPN") "CGA2B1X7R1C104K050BC"))
      (libsource (lib "eagle-import") (part "C-EUC0402"))
    )
    (comp (ref "C32")
      (value "DNP")
      (footprint "eagle-import:C0402")
      (fields (field (name "MPN") "GCM1555C1H101JA16D "))
      (libsource (lib "eagle-import") (part "C-EUC0402"))
    )
    (comp (ref "C33")
      (value "100p")
      (footprint "eagle-import:C0402")
      (fields (field (name "MPN") "GCM1555C1H101JA16D "))
      (libsource (lib "eagle-import") (part "C-EUC0402"))
    )
    (comp (ref "J2")
      (value "73415-2061")
      (footprint "eagle-import:73415-2063")
      (fields (field (name "MPN") "0734152061"))
      (libsource (lib "eagle-import") (part "73415-2061"))
    )
    (comp (ref "R24")
      (value "10k")
      (footprint "eagle-import:.0603-B-NOSILK")
      (fields (field (name "MPN") "ERJ-3EKF1002V"))
      (libsource (lib "eagle-import") (part "rcl_custom_R-US_0603-B-NOSILK"))
    )
    (comp (ref "R25")
      (value "5.62k")
      (footprint "eagle-import:.0603-B-NOSILK")
      (fields (field (name "MPN") "ERJ-3EKF5621V"))
      (libsource (lib "eagle-import") (part "rcl_custom_R-US_0603-B-NOSILK"))
    )
    (comp (ref "R26")
      (value "10k")
      (footprint "eagle-import:.0603-B-NOSILK")
      (fields (field (name "MPN") "ERJ-3EKF1002V"))
      (libsource (lib "eagle-import") (part "rcl_custom_R-US_0603-B-NOSILK"))
    )
    (comp (ref "R27")
      (value "5.62k")
      (footprint "eagle-import:.0603-B-NOSILK")
      (fields (field (name "MPN") "ERJ-3EKF5621V"))
      (libsource (lib "eagle-import") (part "rcl_custom_R-US_0603-B-NOSILK"))
    )
    (comp (ref "U8")
      (value "QPC1022")
      (footprint "eagle-import:QPC1022")
      (libsource (lib "eagle-import") (part "QPC1022"))
    )
    (comp (ref "C26")
      (value "15p")
      (footprint "eagle-import:C0402")
      (fields (field (name "MPN") "GJM1555C1H150JB01D "))
      (libsource (lib "eagle-import") (part "C-EUC0402"))
    )
    (comp (ref "C27")
      (value "15p")
      (footprint "eagle-import:C0402")
      (fields (field (name "MPN") "GJM1555C1H150JB01D "))
      (libsource (lib "eagle-import") (part "C-EUC0402"))
    )
    (comp (ref "C28")
      (value "15p")
      (footprint "eagle-import:C0402")
      (fields (field (name "MPN") "GJM1555C1H150JB01D "))
      (libsource (lib "eagle-import") (part "C-EUC0402"))
    )
    (comp (ref "C29")
      (value "1uF")
      (footprint "eagle-import:C0603")
      (fields (field (name "MPN") "C0603X105M4RACAUTO "))
      (libsource (lib "eagle-import") (part "C-EUC0603"))
    )
    (comp (ref "FL1")
      (value "885071-A")
      (footprint "eagle-import:FIL_B39162B9417K610")
      (libsource (lib "eagle-import") (part "885071-A"))
    )
    (comp (ref "FL2")
      (value "885071-A")
      (footprint "eagle-import:FIL_B39162B9417K610")
      (libsource (lib "eagle-import") (part "885071-A"))
    )
    (comp (ref "L4")
      (value "68nH")
      (footprint "eagle-import:0603CS-68NXJLW")
      (fields (field (name "MPN") "0603CS-68NXJLW"))
      (libsource (lib "eagle-import") (part "0603CS-68NXJLW"))
    )
    (comp (ref "L5")
      (value "7.5nH")
      (footprint "eagle-import:0402CS1N2XJLW")
      (fields
        (field (name "MANUFACTURER_PART_NUMBER") "0402CS-1N2XJLW")
        (field (name "MANUFACTURER_PART_NUMBER_1") "0402CS-7N5XGLU")
      )
      (libsource (lib "eagle-import") (part "0402CS-1N2XJLW"))
    )
    (comp (ref "L6")
      (value "8.2nH")
      (footprint "eagle-import:0402CS1N2XJLW")
      (fields
        (field (name "MANUFACTURER_PART_NUMBER") "0402CS-1N2XJLW")
        (field (name "MANUFACTURER_PART_NUMBER_1") "0402CS-8N2XGLU")
      )
      (libsource (lib "eagle-import") (part "0402CS-1N2XJLW"))
    )
    (comp (ref "L7")
      (value "7.5nH")
      (footprint "eagle-import:0402CS1N2XJLW")
      (fields
        (field (name "MANUFACTURER_PART_NUMBER") "0402CS-1N2XJLW")
        (field (name "MANUFACTURER_PART_NUMBER_1") "0402CS-7N5XGLU")
      )
      (libsource (lib "eagle-import") (part "0402CS-1N2XJLW"))
    )
    (comp (ref "L8")
      (value "8.2nH")
      (footprint "eagle-import:0402CS1N2XJLW")
      (fields
        (field (name "MANUFACTURER_PART_NUMBER") "0402CS-1N2XJLW")
        (field (name "MANUFACTURER_PART_NUMBER_1") "0402CS-8N2XGLU")
      )
      (libsource (lib "eagle-import") (part "0402CS-1N2XJLW"))
    )
    (comp (ref "R21")
      (value "10k")
      (footprint "eagle-import:R0603")
      (fields (field (name "MPN") "ERJ-3EKF1002V"))
      (libsource (lib "eagle-import") (part "rcl_334_R-US_R0603"))
    )
    (comp (ref "R22")
      (value "33k")
      (footprint "eagle-import:R0603")
      (fields (field (name "MPN") "ERJ-3GEYJ333V"))
      (libsource (lib "eagle-import") (part "rcl_334_R-US_R0603"))
    )
    (comp (ref "R23")
      (value "0")
      (footprint "eagle-import:R0603")
      (fields (field (name "MPN") "ERJ-3GEY0R00V"))
      (libsource (lib "eagle-import") (part "rcl_334_R-US_R0603"))
    )
    (comp (ref "U7")
      (value "TQP3M9035")
      (footprint "eagle-import:DFN-8")
      (libsource (lib "eagle-import") (part "TQP3M9035"))
    )
    (comp (ref "C15")
      (value "100nF")
      (footprint "eagle-import:C0603")
      (fields (field (name "MPN") "C0603C104K5RACAUTO "))
      (libsource (lib "eagle-import") (part "C-EUC0603"))
    )
    (comp (ref "C16")
      (value "100nF")
      (footprint "eagle-import:C0603")
      (fields (field (name "MPN") "C0603C104K5RACAUTO "))
      (libsource (lib "eagle-import") (part "C-EUC0603"))
    )
    (comp (ref "C17")
      (value "100nF")
      (footprint "eagle-import:C0603")
      (fields (field (name "MPN") "C0603C104K5RACAUTO "))
      (libsource (lib "eagle-import") (part "C-EUC0603"))
    )
    (comp (ref "C18")
      (value "100nF")
      (footprint "eagle-import:C0603")
      (fields (field (name "MPN") "C0603C104K5RACAUTO "))
      (libsource (lib "eagle-import") (part "C-EUC0603"))
    )
    (comp (ref "C19")
      (value "1000pF")
      (footprint "eagle-import:C0603")
      (fields (field (name "MPN") "CGA3E2C0G1H102J080AA"))
      (libsource (lib "eagle-import") (part "C-EUC0603"))
    )
    (comp (ref "C20")
      (value "100pF")
      (footprint "eagle-import:C0603")
      (fields (field (name "MPN") "GCM1885C1H101JA16D "))
      (libsource (lib "eagle-import") (part "C-EUC0603"))
    )
    (comp (ref "C21")
      (value "3.0pF")
      (footprint "eagle-import:C0402")
      (fields (field (name "MPN") "UVK105CG030JW-F"))
      (libsource (lib "eagle-import") (part "C-EUC0402"))
    )
    (comp (ref "C22")
      (value "2.2pF")
      (footprint "eagle-import:C0402")
      (fields (field (name "MPN") "UVK105CG2R2JW-F"))
      (libsource (lib "eagle-import") (part "C-EUC0402"))
    )
    (comp (ref "C23")
      (value "1.6pF")
      (footprint "eagle-import:C0402")
      (fields (field (name "MPN") "GJM1555C1H1R6BB01D"))
      (libsource (lib "eagle-import") (part "C-EUC0402"))
    )
    (comp (ref "C24")
      (value "4.7pF")
      (footprint "eagle-import:C0603")
      (fields (field (name "MPN") "06032U4R7BAT2A "))
      (libsource (lib "eagle-import") (part "C-EUC0603"))
    )
    (comp (ref "L1")
      (value "10nH")
      (footprint "eagle-import:INDC2928X203N")
      (fields (field (name "MANUFACTURER_PART_NUMBER") "1008HQ-10NXJLB"))
      (libsource (lib "eagle-import") (part "1008HQ-10NXJLB"))
    )
    (comp (ref "L2")
      (value "6.8nH")
      (footprint "eagle-import:0805CS")
      (fields (field (name "MANUFACTURER_PART_NUMBER") "0805CS-060XJLC"))
      (libsource (lib "eagle-import") (part "0805CS-060XJLC"))
    )
    (comp (ref "L3")
      (value "1.2nH")
      (footprint "eagle-import:0402CS1N2XJLW")
      (fields (field (name "MANUFACTURER_PART_NUMBER") "0402CS-1N2XJLW"))
      (libsource (lib "eagle-import") (part "0402CS-1N2XJLW"))
    )
    (comp (ref "R17")
      (value "0")
      (footprint "eagle-import:R0805")
      (fields (field (name "MPN") "ERJ-6GEY0R00V"))
      (libsource (lib "eagle-import") (part "rcl_334_R-US_R0805"))
    )
    (comp (ref "R18")
      (value "1.2")
      (footprint "eagle-import:R0402")
      (fields (field (name "MPN") "ERJ-2GEJ1R2X"))
      (libsource (lib "eagle-import") (part "rcl_334_R-US_R0402"))
    )
    (comp (ref "R19")
      (value "110")
      (footprint "eagle-import:R0603")
      (fields (field (name "MPN") "ERJ-3EKF1100V"))
      (libsource (lib "eagle-import") (part "rcl_334_R-US_R0603"))
    )
    (comp (ref "R20")
      (value "220")
      (footprint "eagle-import:R0603")
      (fields (field (name "MPN") "ERJ-3EKF2200V"))
      (libsource (lib "eagle-import") (part "rcl_334_R-US_R0603"))
    )
    (comp (ref "U6")
      (value "TQP9111")
      (footprint "eagle-import:QFN50P400X400X102-21N")
      (libsource (lib "eagle-import") (part "TQP9111"))
    )
    (comp (ref "CF1")
      (value "CON-MMCX-F-MOLEX-0734151001")
      (footprint "eagle-import:CON-MMCX-F-MOLEX-0734151001")
      (fields (field (name "MPN") "0734151001"))
      (libsource (lib "eagle-import") (part "CON-MMCX-F-MOLEX-0734151001"))
    )
    (comp (ref "FL3")
      (value "885071-A")
      (footprint "eagle-import:FIL_B39162B9417K610")
      (libsource (lib "eagle-import") (part "885071-A"))
    )
    (comp (ref "J4")
      (value "73415-2061")
      (footprint "eagle-import:73415-2063")
      (fields (field (name "MPN") "0734152061"))
      (libsource (lib "eagle-import") (part "73415-2061"))
    )
    (comp (ref "J5")
      (value "73415-2061")
      (footprint "eagle-import:73415-2063")
      (fields (field (name "MPN") "0734152061"))
      (libsource (lib "eagle-import") (part "73415-2061"))
    )
    (comp (ref "J6")
      (value "73415-2061")
      (footprint "eagle-import:73415-2063")
      (fields (field (name "MPN") "0734152061"))
      (libsource (lib "eagle-import") (part "73415-2061"))
    )
    (comp (ref "J7")
      (value "73415-2061")
      (footprint "eagle-import:73415-2063")
      (fields (field (name "MPN") "0734152061"))
      (libsource (lib "eagle-import") (part "73415-2061"))
    )
    (comp (ref "J8")
      (value "73415-2061")
      (footprint "eagle-import:73415-2063")
      (fields (field (name "MPN") "0734152061"))
      (libsource (lib "eagle-import") (part "73415-2061"))
    )
    (comp (ref "L11")
      (value "7.5nH")
      (footprint "eagle-import:0402CS1N2XJLW")
      (fields
        (field (name "MANUFACTURER_PART_NUMBER") "0402CS-1N2XJLW")
        (field (name "MANUFACTURER_PART_NUMBER_1") "0402CS-7N5XGLU")
      )
      (libsource (lib "eagle-import") (part "0402CS-1N2XJLW"))
    )
    (comp (ref "L12")
      (value "8.2nH")
      (footprint "eagle-import:0402CS1N2XJLW")
      (fields
        (field (name "MANUFACTURER_PART_NUMBER") "0402CS-1N2XJLW")
        (field (name "MANUFACTURER_PART_NUMBER_1") "0402CS-8N2XGLU")
      )
      (libsource (lib "eagle-import") (part "0402CS-1N2XJLW"))
    )
    (comp (ref "R33")
      (value "49.9")
      (footprint "eagle-import:R0603")
      (fields (field (name "MPN") "ERJ-3EKF49R9V"))
      (libsource (lib "eagle-import") (part "rcl_334_R-US_R0603"))
    )
    (comp (ref "R34")
      (value "49.9")
      (footprint "eagle-import:R0603")
      (fields (field (name "MPN") "ERJ-3EKF49R9V"))
      (libsource (lib "eagle-import") (part "rcl_334_R-US_R0603"))
    )
    (comp (ref "R35")
      (value "0")
      (footprint "eagle-import:.0402-A")
      (fields (field (name "MPN") "ERJ-2GE0R00X"))
      (libsource (lib "eagle-import") (part "R-US_0402-A"))
    )
    (comp (ref "C9")
      (value "100p")
      (footprint "eagle-import:C0402")
      (fields (field (name "MPN") "GCM1555C1H101JA16D "))
      (libsource (lib "eagle-import") (part "C-EUC0402"))
    )
    (comp (ref "C10")
      (value "100n")
      (footprint "eagle-import:C0402")
      (fields (field (name "MPN") "CGA2B1X7R1C104K050BC"))
      (libsource (lib "eagle-import") (part "C-EUC0402"))
    )
    (comp (ref "C11")
      (value "DNP")
      (footprint "eagle-import:C0402")
      (fields (field (name "MPN") "GCM1555C1H101JA16D "))
      (libsource (lib "eagle-import") (part "C-EUC0402"))
    )
    (comp (ref "C12")
      (value "100p")
      (footprint "eagle-import:C0402")
      (fields (field (name "MPN") "GCM1555C1H101JA16D "))
      (libsource (lib "eagle-import") (part "C-EUC0402"))
    )
    (comp (ref "C13")
      (value "100p")
      (footprint "eagle-import:C0402")
      (fields (field (name "MPN") "GCM1555C1H101JA16D "))
      (libsource (lib "eagle-import") (part "C-EUC0402"))
    )
    (comp (ref "C14")
      (value "100n")
      (footprint "eagle-import:C0402")
      (fields (field (name "MPN") "CGA2B1X7R1C104K050BC"))
      (libsource (lib "eagle-import") (part "C-EUC0402"))
    )
    (comp (ref "R1")
      (value "147")
      (footprint "eagle-import:R0603")
      (fields (field (name "MPN") "ERJ-3EKF1470V"))
      (libsource (lib "eagle-import") (part "rcl_334_R-US_R0603"))
    )
    (comp (ref "R2")
      (value "147")
      (footprint "eagle-import:R0603")
      (fields (field (name "MPN") "ERJ-3EKF1470V"))
      (libsource (lib "eagle-import") (part "rcl_334_R-US_R0603"))
    )
    (comp (ref "R3")
      (value "17.8")
      (footprint "eagle-import:R0603")
      (fields (field (name "MPN") "ERJ-3EKF17R8V"))
      (libsource (lib "eagle-import") (part "rcl_334_R-US_R0603"))
    )
    (comp (ref "R4")
      (value "294")
      (footprint "eagle-import:R0603")
      (fields (field (name "MPN") "ERJ-3EKF2940V"))
      (libsource (lib "eagle-import") (part "rcl_334_R-US_R0603"))
    )
    (comp (ref "R13")
      (value "10k")
      (footprint "eagle-import:.0603-B-NOSILK")
      (fields (field (name "MPN") "ERJ-3EKF1002V"))
      (libsource (lib "eagle-import") (part "rcl_custom_R-US_0603-B-NOSILK"))
    )
    (comp (ref "R14")
      (value "5.62k")
      (footprint "eagle-import:.0603-B-NOSILK")
      (fields (field (name "MPN") "ERJ-3EKF5621V"))
      (libsource (lib "eagle-import") (part "rcl_custom_R-US_0603-B-NOSILK"))
    )
    (comp (ref "R15")
      (value "10k")
      (footprint "eagle-import:.0603-B-NOSILK")
      (fields (field (name "MPN") "ERJ-3EKF1002V"))
      (libsource (lib "eagle-import") (part "rcl_custom_R-US_0603-B-NOSILK"))
    )
    (comp (ref "R16")
      (value "5.62k")
      (footprint "eagle-import:.0603-B-NOSILK")
      (fields (field (name "MPN") "ERJ-3EKF5621V"))
      (libsource (lib "eagle-import") (part "rcl_custom_R-US_0603-B-NOSILK"))
    )
    (comp (ref "U4")
      (value "QPC1022")
      (footprint "eagle-import:QPC1022")
      (fields (field (name "MPN") "QPC1022SR"))
      (libsource (lib "eagle-import") (part "QPC1022"))
    )
    (comp (ref "U5")
      (value "NC7S04M5")
      (footprint "eagle-import:SOT95P280X140-5N")
      (fields
        (field (name "ARROW_PART_NUMBER") "NC7S04M5XX")
        (field (name "RS_PART_NUMBER") "6709769")
        (field (name "MANUFACTURER_PART_NUMBER") "NC7S04M5X")
      )
      (libsource (lib "eagle-import") (part "NC7S04M5XX"))
    )
  )
  (nets
    (net (code "1") (name "+5V") (class "Default")
      (node (ref "C10") (pin "1") (pinfunction "1_1") (pintype "passive"))
      (node (ref "C13") (pin "1") (pinfunction "1_1") (pintype "passive"))
      (node (ref "C14") (pin "1") (pinfunction "1_1") (pintype "passive"))
      (node (ref "C3") (pin "1") (pinfunction "1_1") (pintype "passive"))
      (node (ref "C30") (pin "1") (pinfunction "1_1") (pintype "passive"))
      (node (ref "C31") (pin "1") (pinfunction "1_1") (pintype "passive"))
      (node (ref "C4") (pin "1") (pinfunction "1_1") (pintype "passive"))
      (node (ref "C5") (pin "1") (pinfunction "1_1") (pintype "passive"))
      (node (ref "C6") (pin "1") (pinfunction "1_1") (pintype "passive"))
      (node (ref "C7") (pin "1") (pinfunction "1_1") (pintype "passive"))
      (node (ref "C8") (pin "1") (pinfunction "1_1") (pintype "passive"))
      (node (ref "C9") (pin "1") (pinfunction "1_1") (pintype "passive"))
      (node (ref "J3") (pin "2") (pinfunction "2_2") (pintype "bidirectional"))
      (node (ref "R13") (pin "1") (pinfunction "1_1") (pintype "passive"))
      (node (ref "R17") (pin "2") (pinfunction "2_2") (pintype "passive"))
      (node (ref "R23") (pin "2") (pinfunction "2_2") (pintype "passive"))
      (node (ref "R24") (pin "1") (pinfunction "1_1") (pintype "passive"))
      (node (ref "R9") (pin "2") (pinfunction "2_2") (pintype "passive"))
      (node (ref "S1") (pin "1") (pinfunction "1_1") (pintype "bidirectional"))
      (node (ref "U1") (pin "6") (pinfunction "VCC_6") (pintype "power_in"))
      (node (ref "U2") (pin "5") (pinfunction "V+_5") (pintype "power_in"))
      (node (ref "U3") (pin "4") (pinfunction "DIV_4") (pintype "input"))
      (node (ref "U3") (pin "5") (pinfunction "V+_5") (pintype "power_in"))
      (node (ref "U4") (pin "7") (pinfunction "VDD_7") (pintype "power_in"))
      (node (ref "U5") (pin "5") (pinfunction "VCC_5") (pintype "power_in"))
      (node (ref "U8") (pin "7") (pinfunction "VDD_7") (pintype "power_in"))
    )
    (net (code "2") (name "GND") (class "Default")
      (node (ref "C10") (pin "2") (pinfunction "2_2") (pintype "passive"))
      (node (ref "C11") (pin "2") (pinfunction "2_2") (pintype "passive"))
      (node (ref "C12") (pin "2") (pinfunction "2_2") (pintype "passive"))
      (node (ref "C13") (pin "2") (pinfunction "2_2") (pintype "passive"))
      (node (ref "C14") (pin "2") (pinfunction "2_2") (pintype "passive"))
      (node (ref "C15") (pin "2") (pinfunction "2_2") (pintype "passive"))
      (node (ref "C16") (pin "2") (pinfunction "2_2") (pintype "passive"))
      (node (ref "C17") (pin "2") (pinfunction "2_2") (pintype "passive"))
      (node (ref "C18") (pin "2") (pinfunction "2_2") (pintype "passive"))
      (node (ref "C19") (pin "2") (pinfunction "2_2") (pintype "passive"))
      (node (ref "C2") (pin "2") (pinfunction "2_2") (pintype "passive"))
      (node (ref "C21") (pin "2") (pinfunction "2_2") (pintype "passive"))
      (node (ref "C22") (pin "2") (pinfunction "2_2") (pintype "passive"))
      (node (ref "C23") (pin "2") (pinfunction "2_2") (pintype "passive"))
      (node (ref "C25") (pin "2") (pinfunction "2_2") (pintype "passive"))
      (node (ref "C27") (pin "1") (pinfunction "1_1") (pintype "passive"))
      (node (ref "C29") (pin "2") (pinfunction "2_2") (pintype "passive"))
      (node (ref "C3") (pin "2") (pinfunction "2_2") (pintype "passive"))
      (node (ref "C30") (pin "2") (pinfunction "2_2") (pintype "passive"))
      (node (ref "C31") (pin "2") (pinfunction "2_2") (pintype "passive"))
      (node (ref "C32") (pin "2") (pinfunction "2_2") (pintype "passive"))
      (node (ref "C33") (pin "2") (pinfunction "2_2") (pintype "passive"))
      (node (ref "C34") (pin "2") (pinfunction "2_2") (pintype "passive"))
      (node (ref "C35") (pin "2") (pinfunction "2_2") (pintype "passive"))
      (node (ref "C37") (pin "2") (pinfunction "2_2") (pintype "passive"))
      (node (ref "C38") (pin "2") (pinfunction "2_2") (pintype "passive"))
      (node (ref "C4") (pin "2") (pinfunction "2_2") (pintype "passive"))
      (node (ref "C5") (pin "2") (pinfunction "2_2") (pintype "passive"))
      (node (ref "C6") (pin "2") (pinfunction "2_2") (pintype "passive"))
      (node (ref "C7") (pin "2") (pinfunction "2_2") (pintype "passive"))
      (node (ref "C8") (pin "2") (pinfunction "2_2") (pintype "passive"))
      (node (ref "C9") (pin "2") (pinfunction "2_2") (pintype "passive"))
      (node (ref "CF1") (pin "G1") (pinfunction "SHIELD_G1") (pintype "passive"))
      (node (ref "CF1") (pin "G2") (pinfunction "SHIELD_G2") (pintype "passive"))
      (node (ref "CF1") (pin "G3") (pinfunction "SHIELD_G3") (pintype "passive"))
      (node (ref "CF1") (pin "G4") (pinfunction "SHIELD_G4") (pintype "passive"))
      (node (ref "FL1") (pin "2") (pinfunction "GND_2") (pintype "power_in"))
      (node (ref "FL1") (pin "3") (pinfunction "GND_3") (pintype "power_in"))
      (node (ref "FL1") (pin "5") (pinfunction "GND_5") (pintype "power_in"))
      (node (ref "FL2") (pin "2") (pinfunction "GND_2") (pintype "power_in"))
      (node (ref "FL2") (pin "3") (pinfunction "GND_3") (pintype "power_in"))
      (node (ref "FL2") (pin "5") (pinfunction "GND_5") (pintype "power_in"))
      (node (ref "FL3") (pin "2") (pinfunction "GND_2") (pintype "power_in"))
      (node (ref "FL3") (pin "3") (pinfunction "GND_3") (pintype "power_in"))
      (node (ref "FL3") (pin "5") (pinfunction "GND_5") (pintype "power_in"))
      (node (ref "J1") (pin "2") (pinfunction "GND_2") (pintype "passive"))
      (node (ref "J1") (pin "3") (pinfunction "GND_3") (pintype "passive"))
      (node (ref "J1") (pin "4") (pinfunction "GND_4") (pintype "passive"))
      (node (ref "J1") (pin "5") (pinfunction "GND_5") (pintype "passive"))
      (node (ref "J2") (pin "2") (pinfunction "GND_2") (pintype "passive"))
      (node (ref "J2") (pin "3") (pinfunction "GND_3") (pintype "passive"))
      (node (ref "J2") (pin "4") (pinfunction "GND_4") (pintype "passive"))
      (node (ref "J2") (pin "5") (pinfunction "GND_5") (pintype "passive"))
      (node (ref "J4") (pin "2") (pinfunction "GND_2") (pintype "passive"))
      (node (ref "J4") (pin "3") (pinfunction "GND_3") (pintype "passive"))
      (node (ref "J4") (pin "4") (pinfunction "GND_4") (pintype "passive"))
      (node (ref "J4") (pin "5") (pinfunction "GND_5") (pintype "passive"))
      (node (ref "J5") (pin "2") (pinfunction "GND_2") (pintype "passive"))
      (node (ref "J5") (pin "3") (pinfunction "GND_3") (pintype "passive"))
      (node (ref "J5") (pin "4") (pinfunction "GND_4") (pintype "passive"))
      (node (ref "J5") (pin "5") (pinfunction "GND_5") (pintype "passive"))
      (node (ref "J6") (pin "2") (pinfunction "GND_2") (pintype "passive"))
      (node (ref "J6") (pin "3") (pinfunction "GND_3") (pintype "passive"))
      (node (ref "J6") (pin "4") (pinfunction "GND_4") (pintype "passive"))
      (node (ref "J6") (pin "5") (pinfunction "GND_5") (pintype "passive"))
      (node (ref "J7") (pin "2") (pinfunction "GND_2") (pintype "passive"))
      (node (ref "J7") (pin "3") (pinfunction "GND_3") (pintype "passive"))
      (node (ref "J7") (pin "4") (pinfunction "GND_4") (pintype "passive"))
      (node (ref "J7") (pin "5") (pinfunction "GND_5") (pintype "passive"))
      (node (ref "J8") (pin "2") (pinfunction "GND_2") (pintype "passive"))
      (node (ref "J8") (pin "3") (pinfunction "GND_3") (pintype "passive"))
      (node (ref "J8") (pin "4") (pinfunction "GND_4") (pintype "passive"))
      (node (ref "J8") (pin "5") (pinfunction "GND_5") (pintype "passive"))
      (node (ref "L11") (pin "1") (pinfunction "1_1") (pintype "bidirectional"))
      (node (ref "L12") (pin "1") (pinfunction "1_1") (pintype "bidirectional"))
      (node (ref "L5") (pin "1") (pinfunction "1_1") (pintype "bidirectional"))
      (node (ref "L6") (pin "1") (pinfunction "1_1") (pintype "bidirectional"))
      (node (ref "L7") (pin "1") (pinfunction "1_1") (pintype "bidirectional"))
      (node (ref "L8") (pin "1") (pinfunction "1_1") (pintype "bidirectional"))
      (node (ref "PD1") (pin "1") (pinfunction "GND_1") (pintype "power_in"))
      (node (ref "PD1") (pin "3") (pinfunction "GND_3") (pintype "power_in"))
      (node (ref "PD1") (pin "5") (pinfunction "GND_5") (pintype "power_in"))
      (node (ref "R10") (pin "1") (pinfunction "1_1") (pintype "passive"))
      (node (ref "R11") (pin "1") (pinfunction "1_1") (pintype "passive"))
      (node (ref "R12") (pin "1") (pinfunction "1_1") (pintype "passive"))
      (node (ref "R14") (pin "2") (pinfunction "2_2") (pintype "passive"))
      (node (ref "R16") (pin "2") (pinfunction "2_2") (pintype "passive"))
      (node (ref "R2") (pin "1") (pinfunction "1_1") (pintype "passive"))
      (node (ref "R22") (pin "1") (pinfunction "1_1") (pintype "passive"))
      (node (ref "R25") (pin "2") (pinfunction "2_2") (pintype "passive"))
      (node (ref "R27") (pin "2") (pinfunction "2_2") (pintype "passive"))
      (node (ref "R29") (pin "1") (pinfunction "1_1") (pintype "passive"))
      (node (ref "R32") (pin "1") (pinfunction "1_1") (pintype "passive"))
      (node (ref "R33") (pin "1") (pinfunction "1_1") (pintype "passive"))
      (node (ref "R34") (pin "1") (pinfunction "1_1") (pintype "passive"))
      (node (ref "R4") (pin "2") (pinfunction "2_2") (pintype "passive"))
      (node (ref "R6") (pin "1") (pinfunction "1_1") (pintype "passive"))
      (node (ref "R8") (pin "2") (pinfunction "2_2") (pintype "passive"))
      (node (ref "S1") (pin "6") (pinfunction "6_6") (pintype "bidirectional"))
      (node (ref "U1") (pin "2") (pinfunction "GND_2") (pintype "power_in"))
      (node (ref "U1") (pin "4") (pinfunction "LEN_4") (pintype "input"))
      (node (ref "U2") (pin "2") (pinfunction "GND_2") (pintype "power_in"))
      (node (ref "U2") (pin "4") (pinfunction "DIV_4") (pintype "input"))
      (node (ref "U3") (pin "2") (pinfunction "GND_2") (pintype "power_in"))
      (node (ref "U4") (pin "1") (pinfunction "GND_1") (pintype "power_in"))
      (node (ref "U4") (pin "3") (pinfunction "GND_3") (pintype "power_in"))
      (node (ref "U4") (pin "9") (pinfunction "GND_9") (pintype "power_in"))
      (node (ref "U5") (pin "3") (pinfunction "GND_3") (pintype "power_in"))
      (node (ref "U6") (pin "21") (pinfunction "GND_21") (pintype "bidirectional"))
      (node (ref "U7") (pin "9") (pinfunction "GND_9") (pintype "power_in"))
      (node (ref "U8") (pin "1") (pinfunction "GND_1") (pintype "power_in"))
      (node (ref "U8") (pin "3") (pinfunction "GND_3") (pintype "power_in"))
      (node (ref "U8") (pin "9") (pinfunction "GND_9") (pintype "power_in"))
      (node (ref "U9") (pin "1") (pinfunction "GND_1") (pintype "power_in"))
      (node (ref "U9") (pin "10") (pinfunction "GND_10") (pintype "power_in"))
      (node (ref "U9") (pin "11") (pinfunction "GND_11") (pintype "passive"))
      (node (ref "U9") (pin "7") (pinfunction "GND_7") (pintype "power_in"))
    )
    (net (code "3") (name "Net-(C1-Pad1)") (class "Default")
      (node (ref "C1") (pin "1") (pinfunction "1_1") (pintype "passive"))
      (node (ref "R7") (pin "2") (pinfunction "2_2") (pintype "passive"))
      (node (ref "R8") (pin "1") (pinfunction "1_1") (pintype "passive"))
    )
    (net (code "4") (name "Net-(C15-Pad1)") (class "Default")
      (node (ref "C15") (pin "1") (pinfunction "1_1") (pintype "passive"))
      (node (ref "C16") (pin "1") (pinfunction "1_1") (pintype "passive"))
      (node (ref "C17") (pin "1") (pinfunction "1_1") (pintype "passive"))
      (node (ref "C19") (pin "1") (pinfunction "1_1") (pintype "passive"))
      (node (ref "L1") (pin "2") (pinfunction "2_2") (pintype "bidirectional"))
      (node (ref "L2") (pin "2") (pinfunction "2_2") (pintype "bidirectional"))
      (node (ref "R17") (pin "1") (pinfunction "1_1") (pintype "passive"))
      (node (ref "R20") (pin "2") (pinfunction "2_2") (pintype "passive"))
    )
    (net (code "5") (name "Net-(C20-Pad1)") (class "Default")
      (node (ref "C20") (pin "1") (pinfunction "1_1") (pintype "passive"))
      (node (ref "C23") (pin "1") (pinfunction "1_1") (pintype "passive"))
      (node (ref "L3") (pin "2") (pinfunction "2_2") (pintype "bidirectional"))
    )
    (net (code "6") (name "Net-(C21-Pad1)") (class "Default")
      (node (ref "C21") (pin "1") (pinfunction "1_1") (pintype "passive"))
      (node (ref "L3") (pin "1") (pinfunction "1_1") (pintype "bidirectional"))
      (node (ref "U6") (pin "12") (pinfunction "RFOUT_12") (pintype "bidirectional"))
      (node (ref "U6") (pin "13") (pinfunction "RFOUT_13") (pintype "bidirectional"))
      (node (ref "U6") (pin "14") (pinfunction "RFOUT_14") (pintype "bidirectional"))
    )
    (net (code "7") (name "Net-(C22-Pad1)") (class "Default")
      (node (ref "C22") (pin "1") (pinfunction "1_1") (pintype "passive"))
      (node (ref "C24") (pin "2") (pinfunction "2_2") (pintype "passive"))
      (node (ref "R18") (pin "1") (pinfunction "1_1") (pintype "passive"))
    )
    (net (code "8") (name "Net-(C27-Pad2)") (class "Default")
      (node (ref "C27") (pin "2") (pinfunction "2_2") (pintype "passive"))
      (node (ref "C29") (pin "1") (pinfunction "1_1") (pintype "passive"))
      (node (ref "L4") (pin "2") (pinfunction "2_2") (pintype "bidirectional"))
      (node (ref "R23") (pin "1") (pinfunction "1_1") (pintype "passive"))
    )
    (net (code "9") (name "Net-(C35-Pad1)") (class "Default")
      (node (ref "C35") (pin "1") (pinfunction "1_1") (pintype "passive"))
      (node (ref "J3") (pin "1") (pinfunction "1_1") (pintype "bidirectional"))
    )
    (net (code "10") (name "Net-(C37-Pad1)") (class "Default")
      (node (ref "C37") (pin "1") (pinfunction "1_1") (pintype "passive"))
      (node (ref "R30") (pin "1") (pinfunction "1_1") (pintype "passive"))
    )
    (net (code "11") (name "Net-(CF1-PadCENTER)") (class "Default")
      (node (ref "CF1") (pin "CENTER") (pinfunction "CENTER_CENTER") (pintype "passive"))
      (node (ref "R34") (pin "2") (pinfunction "2_2") (pintype "passive"))
    )
    (net (code "12") (name "Net-(FL1-OUT)") (class "Default")
      (node (ref "C26") (pin "1") (pinfunction "1_1") (pintype "passive"))
      (node (ref "FL1") (pin "4") (pinfunction "OUT_4") (pintype "passive"))
      (node (ref "L6") (pin "2") (pinfunction "2_2") (pintype "bidirectional"))
    )
    (net (code "13") (name "Net-(FL2-IN)") (class "Default")
      (node (ref "C28") (pin "2") (pinfunction "2_2") (pintype "passive"))
      (node (ref "FL2") (pin "1") (pinfunction "IN_1") (pintype "passive"))
      (node (ref "L7") (pin "2") (pinfunction "2_2") (pintype "bidirectional"))
    )
    (net (code "14") (name "Net-(FL3-IN)") (class "Default")
      (node (ref "FL3") (pin "1") (pinfunction "IN_1") (pintype "passive"))
      (node (ref "J4") (pin "1") (pinfunction "CTR_1") (pintype "passive"))
      (node (ref "L11") (pin "2") (pinfunction "2_2") (pintype "bidirectional"))
    )
    (net (code "15") (name "Net-(FL3-OUT)") (class "Default")
      (node (ref "FL3") (pin "4") (pinfunction "OUT_4") (pintype "passive"))
      (node (ref "L12") (pin "2") (pinfunction "2_2") (pintype "bidirectional"))
      (node (ref "R35") (pin "1") (pinfunction "1_1") (pintype "passive"))
    )
    (net (code "16") (name "Net-(J1-CTR)") (class "Default")
      (node (ref "J1") (pin "1") (pinfunction "CTR_1") (pintype "passive"))
      (node (ref "PD1") (pin "2") (pinfunction "IN_2") (pintype "input"))
    )
    (net (code "17") (name "Net-(J2-CTR)") (class "Default")
      (node (ref "J2") (pin "1") (pinfunction "CTR_1") (pintype "passive"))
      (node (ref "U8") (pin "2") (pinfunction "RF_COM_2") (pintype "bidirectional"))
    )
    (net (code "18") (name "Net-(J5-CTR)") (class "Default")
      (node (ref "J5") (pin "1") (pinfunction "CTR_1") (pintype "passive"))
      (node (ref "R35") (pin "2") (pinfunction "2_2") (pintype "passive"))
    )
    (net (code "19") (name "Net-(J6-CTR)") (class "Default")
      (node (ref "J6") (pin "1") (pinfunction "CTR_1") (pintype "passive"))
      (node (ref "J7") (pin "1") (pinfunction "CTR_1") (pintype "passive"))
    )
    (net (code "20") (name "Net-(J8-CTR)") (class "Default")
      (node (ref "J8") (pin "1") (pinfunction "CTR_1") (pintype "passive"))
      (node (ref "R33") (pin "2") (pinfunction "2_2") (pintype "passive"))
    )
    (net (code "21") (name "Net-(LED1-A)") (class "Default")
      (node (ref "LED1") (pin "2") (pinfunction "A_2") (pintype "bidirectional"))
      (node (ref "S1") (pin "2") (pinfunction "2_2") (pintype "bidirectional"))
      (node (ref "U2") (pin "1") (pinfunction "IN_1") (pintype "input"))
      (node (ref "U3") (pin "1") (pinfunction "IN_1") (pintype "input"))
    )
    (net (code "22") (name "Net-(LED1-K)") (class "Default")
      (node (ref "LED1") (pin "1") (pinfunction "K_1") (pintype "bidirectional"))
      (node (ref "R32") (pin "2") (pinfunction "2_2") (pintype "passive"))
    )
    (net (code "23") (name "Net-(PD1-OUT1)") (class "Default")
      (node (ref "PD1") (pin "4") (pinfunction "OUT1_4") (pintype "output"))
      (node (ref "R5") (pin "2") (pinfunction "2_2") (pintype "passive"))
      (node (ref "R7") (pin "1") (pinfunction "1_1") (pintype "passive"))
    )
    (net (code "24") (name "Net-(R1-Pad1)") (class "Default")
      (node (ref "R1") (pin "1") (pinfunction "1_1") (pintype "passive"))
      (node (ref "R2") (pin "2") (pinfunction "2_2") (pintype "passive"))
    )
    (net (code "25") (name "Net-(R5-Pad1)") (class "Default")
      (node (ref "R5") (pin "1") (pinfunction "1_1") (pintype "passive"))
      (node (ref "R6") (pin "2") (pinfunction "2_2") (pintype "passive"))
    )
    (net (code "26") (name "Net-(R18-Pad2)") (class "Default")
      (node (ref "R18") (pin "2") (pinfunction "2_2") (pintype "passive"))
      (node (ref "U6") (pin "2") (pinfunction "RFIN_2") (pintype "bidirectional"))
      (node (ref "U6") (pin "3") (pinfunction "RFIN_3") (pintype "bidirectional"))
      (node (ref "U6") (pin "4") (pinfunction "RFIN_4") (pintype "bidirectional"))
    )
    (net (code "27") (name "Net-(S1-Pad3)") (class "Default")
      (node (ref "S1") (pin "3") (pinfunction "3_3") (pintype "bidirectional"))
      (node (ref "S1") (pin "5") (pinfunction "5_5") (pintype "bidirectional"))
    )
    (net (code "28") (name "Net-(U1-RFIN)") (class "Default")
      (node (ref "C1") (pin "2") (pinfunction "2_2") (pintype "passive"))
      (node (ref "U1") (pin "1") (pinfunction "RFIN_1") (pintype "input"))
    )
    (net (code "29") (name "Net-(U1-VM)") (class "Default")
      (node (ref "C2") (pin "1") (pinfunction "1_1") (pintype "passive"))
      (node (ref "R10") (pin "2") (pinfunction "2_2") (pintype "passive"))
      (node (ref "R9") (pin "1") (pinfunction "1_1") (pintype "passive"))
      (node (ref "U1") (pin "3") (pinfunction "VM_3") (pintype "input"))
    )
    (net (code "30") (name "Net-(U1-VOUT)") (class "Default")
      (node (ref "S1") (pin "4") (pinfunction "4_4") (pintype "bidirectional"))
      (node (ref "U1") (pin "5") (pinfunction "VOUT_5") (pintype "output"))
    )
    (net (code "31") (name "Net-(U2-SET)") (class "Default")
      (node (ref "R11") (pin "2") (pinfunction "2_2") (pintype "passive"))
      (node (ref "U2") (pin "3") (pinfunction "SET_3") (pintype "input"))
    )
    (net (code "32") (name "Net-(U3-SET)") (class "Default")
      (node (ref "R12") (pin "2") (pinfunction "2_2") (pintype "passive"))
      (node (ref "U3") (pin "3") (pinfunction "SET_3") (pintype "input"))
    )
    (net (code "33") (name "Net-(U4-CTRL)") (class "Default")
      (node (ref "C11") (pin "1") (pinfunction "1_1") (pintype "passive"))
      (node (ref "R15") (pin "2") (pinfunction "2_2") (pintype "passive"))
      (node (ref "R16") (pin "1") (pinfunction "1_1") (pintype "passive"))
      (node (ref "U4") (pin "5") (pinfunction "CTRL_5") (pintype "bidirectional"))
    )
    (net (code "34") (name "Net-(U4-EN)") (class "Default")
      (node (ref "C12") (pin "1") (pinfunction "1_1") (pintype "passive"))
      (node (ref "R13") (pin "2") (pinfunction "2_2") (pintype "passive"))
      (node (ref "R14") (pin "1") (pinfunction "1_1") (pintype "passive"))
      (node (ref "U4") (pin "6") (pinfunction "EN_6") (pintype "bidirectional"))
    )
    (net (code "35") (name "Net-(U4-RF2)") (class "Default")
      (node (ref "R1") (pin "2") (pinfunction "2_2") (pintype "passive"))
      (node (ref "R3") (pin "1") (pinfunction "1_1") (pintype "passive"))
      (node (ref "U4") (pin "8") (pinfunction "RF2_8") (pintype "bidirectional"))
    )
    (net (code "36") (name "Net-(U5-Y)") (class "Default")
      (node (ref "R15") (pin "1") (pinfunction "1_1") (pintype "passive"))
      (node (ref "U5") (pin "4") (pinfunction "Y_4") (pintype "output"))
    )
    (net (code "37") (name "Net-(U6-IREF2)") (class "Default")
      (node (ref "C18") (pin "1") (pinfunction "1_1") (pintype "passive"))
      (node (ref "R19") (pin "2") (pinfunction "2_2") (pintype "passive"))
      (node (ref "U6") (pin "8") (pinfunction "IREF2_8") (pintype "bidirectional"))
    )
    (net (code "38") (name "Net-(U6-VBIAS)") (class "Default")
      (node (ref "R20") (pin "1") (pinfunction "1_1") (pintype "passive"))
      (node (ref "U6") (pin "16") (pinfunction "VBIAS_16") (pintype "bidirectional"))
    )
    (net (code "39") (name "Net-(U6-VCC1)") (class "Default")
      (node (ref "L2") (pin "1") (pinfunction "1_1") (pintype "bidirectional"))
      (node (ref "U6") (pin "20") (pinfunction "VCC1_20") (pintype "bidirectional"))
    )
    (net (code "40") (name "Net-(U6-VCC2)") (class "Default")
      (node (ref "L1") (pin "1") (pinfunction "1_1") (pintype "bidirectional"))
      (node (ref "U6") (pin "18") (pinfunction "VCC2_18") (pintype "bidirectional"))
    )
    (net (code "41") (name "Net-(U7-RFIN)") (class "Default")
      (node (ref "C26") (pin "2") (pinfunction "2_2") (pintype "passive"))
      (node (ref "U7") (pin "2") (pinfunction "RFIN_2") (pintype "bidirectional"))
    )
    (net (code "42") (name "Net-(U7-RFOUT)") (class "Default")
      (node (ref "C28") (pin "1") (pinfunction "1_1") (pintype "passive"))
      (node (ref "L4") (pin "1") (pinfunction "1_1") (pintype "bidirectional"))
      (node (ref "U7") (pin "7") (pinfunction "RFOUT_7") (pintype "bidirectional"))
    )
    (net (code "43") (name "Net-(U7-SHUTDN)") (class "Default")
      (node (ref "R21") (pin "1") (pinfunction "1_1") (pintype "passive"))
      (node (ref "R22") (pin "2") (pinfunction "2_2") (pintype "passive"))
      (node (ref "U7") (pin "6") (pinfunction "SHUTDN_6") (pintype "bidirectional"))
    )
    (net (code "44") (name "Net-(U8-CTRL)") (class "Default")
      (node (ref "C32") (pin "1") (pinfunction "1_1") (pintype "passive"))
      (node (ref "R26") (pin "2") (pinfunction "2_2") (pintype "passive"))
      (node (ref "R27") (pin "1") (pinfunction "1_1") (pintype "passive"))
      (node (ref "U8") (pin "5") (pinfunction "CTRL_5") (pintype "bidirectional"))
    )
    (net (code "45") (name "Net-(U8-EN)") (class "Default")
      (node (ref "C33") (pin "1") (pinfunction "1_1") (pintype "passive"))
      (node (ref "R24") (pin "2") (pinfunction "2_2") (pintype "passive"))
      (node (ref "R25") (pin "1") (pinfunction "1_1") (pintype "passive"))
      (node (ref "U8") (pin "6") (pinfunction "EN_6") (pintype "bidirectional"))
    )
    (net (code "46") (name "Net-(U9-FB)") (class "Default")
      (node (ref "R28") (pin "1") (pinfunction "1_1") (pintype "passive"))
      (node (ref "R29") (pin "2") (pinfunction "2_2") (pintype "passive"))
      (node (ref "U9") (pin "6") (pinfunction "FB_6") (pintype "passive"))
    )
    (net (code "47") (name "Net-(U9-SWA)") (class "Default")
      (node (ref "D1") (pin "A") (pinfunction "A_A") (pintype "passive"))
      (node (ref "L9") (pin "1") (pinfunction "1_1") (pintype "bidirectional"))
      (node (ref "U9") (pin "2") (pinfunction "SWA_2") (pintype "passive"))
    )
    (net (code "48") (name "Net-(U9-SWB)") (class "Default")
      (node (ref "D2") (pin "A") (pinfunction "A_A") (pintype "passive"))
      (node (ref "L10") (pin "1") (pinfunction "1_1") (pintype "bidirectional"))
      (node (ref "U9") (pin "9") (pinfunction "SWB_9") (pintype "passive"))
    )
    (net (code "49") (name "Net-(U9-VC)") (class "Default")
      (node (ref "C38") (pin "1") (pinfunction "1_1") (pintype "passive"))
      (node (ref "R30") (pin "2") (pinfunction "2_2") (pintype "passive"))
      (node (ref "U9") (pin "5") (pinfunction "VC_5") (pintype "output"))
    )
    (net (code "50") (name "Net-(U9-VIN)") (class "Default")
      (node (ref "C34") (pin "1") (pinfunction "1_1") (pintype "passive"))
      (node (ref "J3") (pin "4") (pinfunction "4_4") (pintype "bidirectional"))
      (node (ref "L10") (pin "2") (pinfunction "2_2") (pintype "bidirectional"))
      (node (ref "L9") (pin "2") (pinfunction "2_2") (pintype "bidirectional"))
      (node (ref "R31") (pin "2") (pinfunction "2_2") (pintype "passive"))
      (node (ref "U9") (pin "8") (pinfunction "VIN_8") (pintype "input"))
    )
    (net (code "51") (name "Net-(U9-VOUT)") (class "Default")
      (node (ref "C25") (pin "1") (pinfunction "1_1") (pintype "passive"))
      (node (ref "D1") (pin "C") (pinfunction "C_C") (pintype "passive"))
      (node (ref "D2") (pin "C") (pinfunction "C_C") (pintype "passive"))
      (node (ref "J3") (pin "3") (pinfunction "3_3") (pintype "bidirectional"))
      (node (ref "R28") (pin "2") (pinfunction "2_2") (pintype "passive"))
      (node (ref "U9") (pin "3") (pinfunction "VOUT_3") (pintype "output"))
    )
    (net (code "52") (name "Net-(U9-~{SHDN})") (class "Default")
      (node (ref "J3") (pin "5") (pinfunction "5_5") (pintype "bidirectional"))
      (node (ref "R31") (pin "1") (pinfunction "1_1") (pintype "passive"))
      (node (ref "U9") (pin "4") (pinfunction "~{SHDN}_4") (pintype "passive"))
    )
    (net (code "53") (name "PA_MATCH_OUT") (class "Default")
      (node (ref "C20") (pin "2") (pinfunction "2_2") (pintype "passive"))
      (node (ref "U8") (pin "4") (pinfunction "RF1_4") (pintype "bidirectional"))
    )
    (net (code "54") (name "PA_ON_LNA_OFF") (class "Default")
      (node (ref "R19") (pin "1") (pinfunction "1_1") (pintype "passive"))
      (node (ref "R21") (pin "2") (pinfunction "2_2") (pintype "passive"))
      (node (ref "U2") (pin "6") (pinfunction "OUT_6") (pintype "output"))
      (node (ref "U6") (pin "6") (pinfunction "IREF1_6") (pintype "bidirectional"))
    )
    (net (code "55") (name "PA_PAD_OUT") (class "Default")
      (node (ref "C24") (pin "1") (pinfunction "1_1") (pintype "passive"))
      (node (ref "R3") (pin "2") (pinfunction "2_2") (pintype "passive"))
      (node (ref "R4") (pin "1") (pinfunction "1_1") (pintype "passive"))
    )
    (net (code "56") (name "POST_LNA_FILTER_OUT") (class "Default")
      (node (ref "FL2") (pin "4") (pinfunction "OUT_4") (pintype "passive"))
      (node (ref "L8") (pin "2") (pinfunction "2_2") (pintype "bidirectional"))
      (node (ref "U4") (pin "4") (pinfunction "RF1_4") (pintype "bidirectional"))
    )
    (net (code "57") (name "PWR_DIV_OUT2") (class "Default")
      (node (ref "PD1") (pin "6") (pinfunction "OUT2_6") (pintype "output"))
      (node (ref "U4") (pin "2") (pinfunction "RF_COM_2") (pintype "bidirectional"))
    )
    (net (code "58") (name "RX_IN") (class "Default")
      (node (ref "FL1") (pin "1") (pinfunction "IN_1") (pintype "passive"))
      (node (ref "L5") (pin "2") (pinfunction "2_2") (pintype "bidirectional"))
      (node (ref "U8") (pin "8") (pinfunction "RF2_8") (pintype "bidirectional"))
    )
    (net (code "59") (name "TX_RX_CTL") (class "Default")
      (node (ref "R26") (pin "1") (pinfunction "1_1") (pintype "passive"))
      (node (ref "U3") (pin "6") (pinfunction "OUT_6") (pintype "output"))
      (node (ref "U5") (pin "2") (pinfunction "A_2") (pintype "input"))
    )
  )
)
